# 2015_IHM.net
KiCad netlist of a schematic drawn in Altium Designer
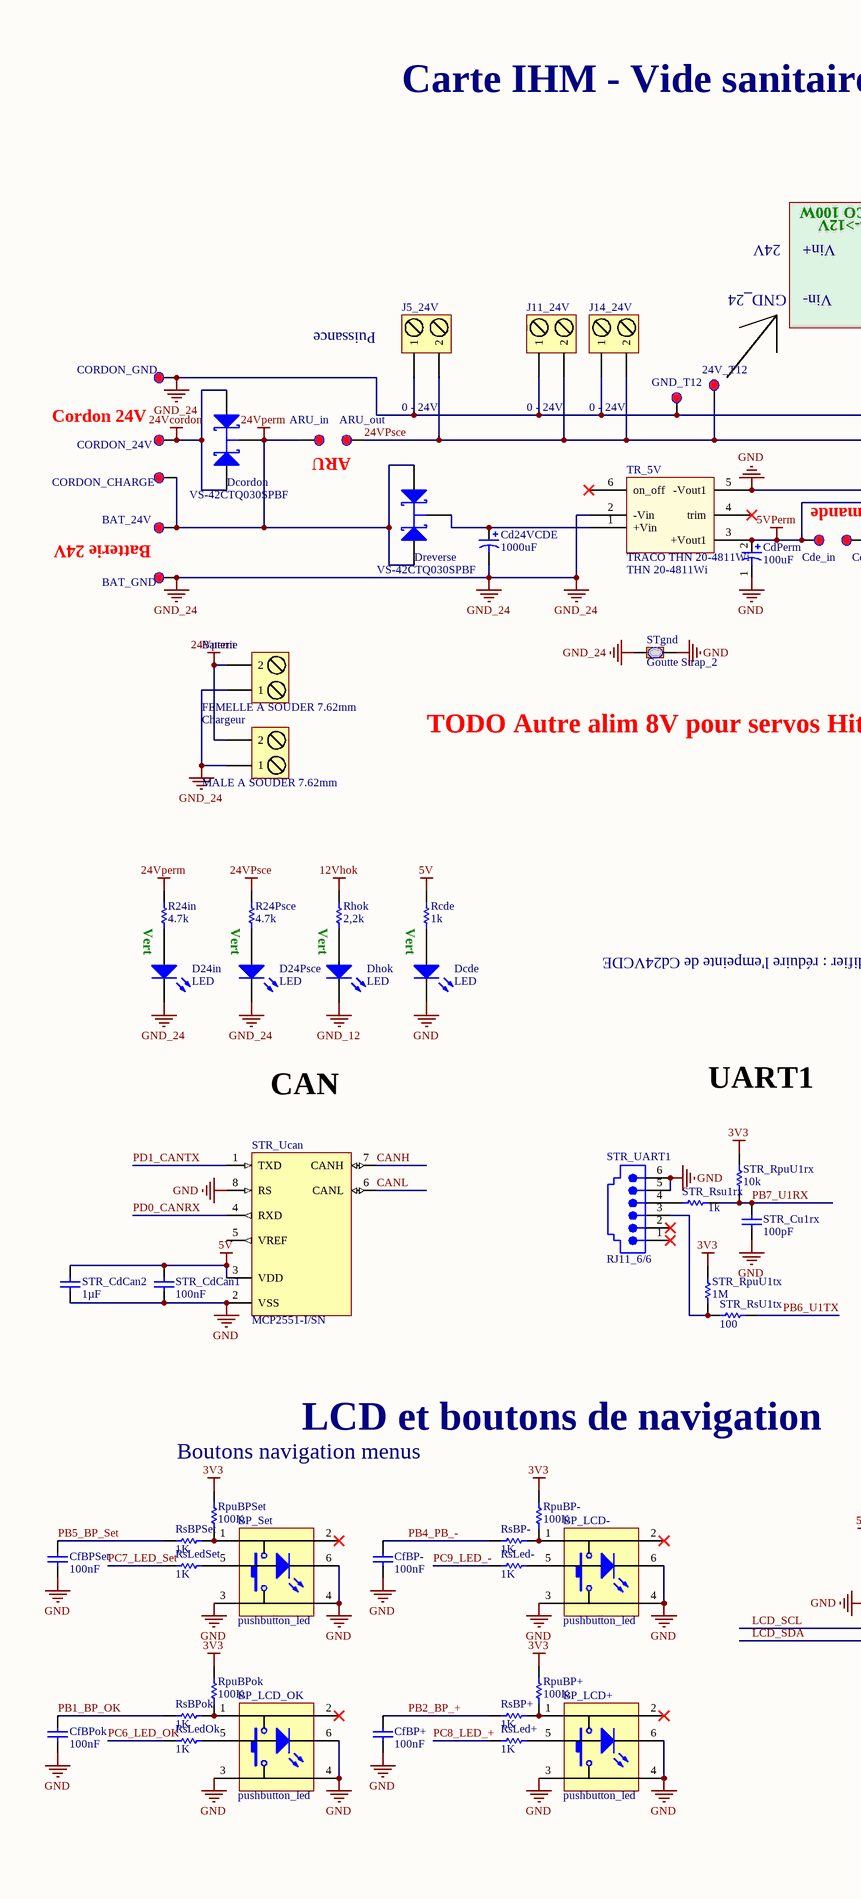
[diagram p0: 2015_IHM.SchDoc, left]
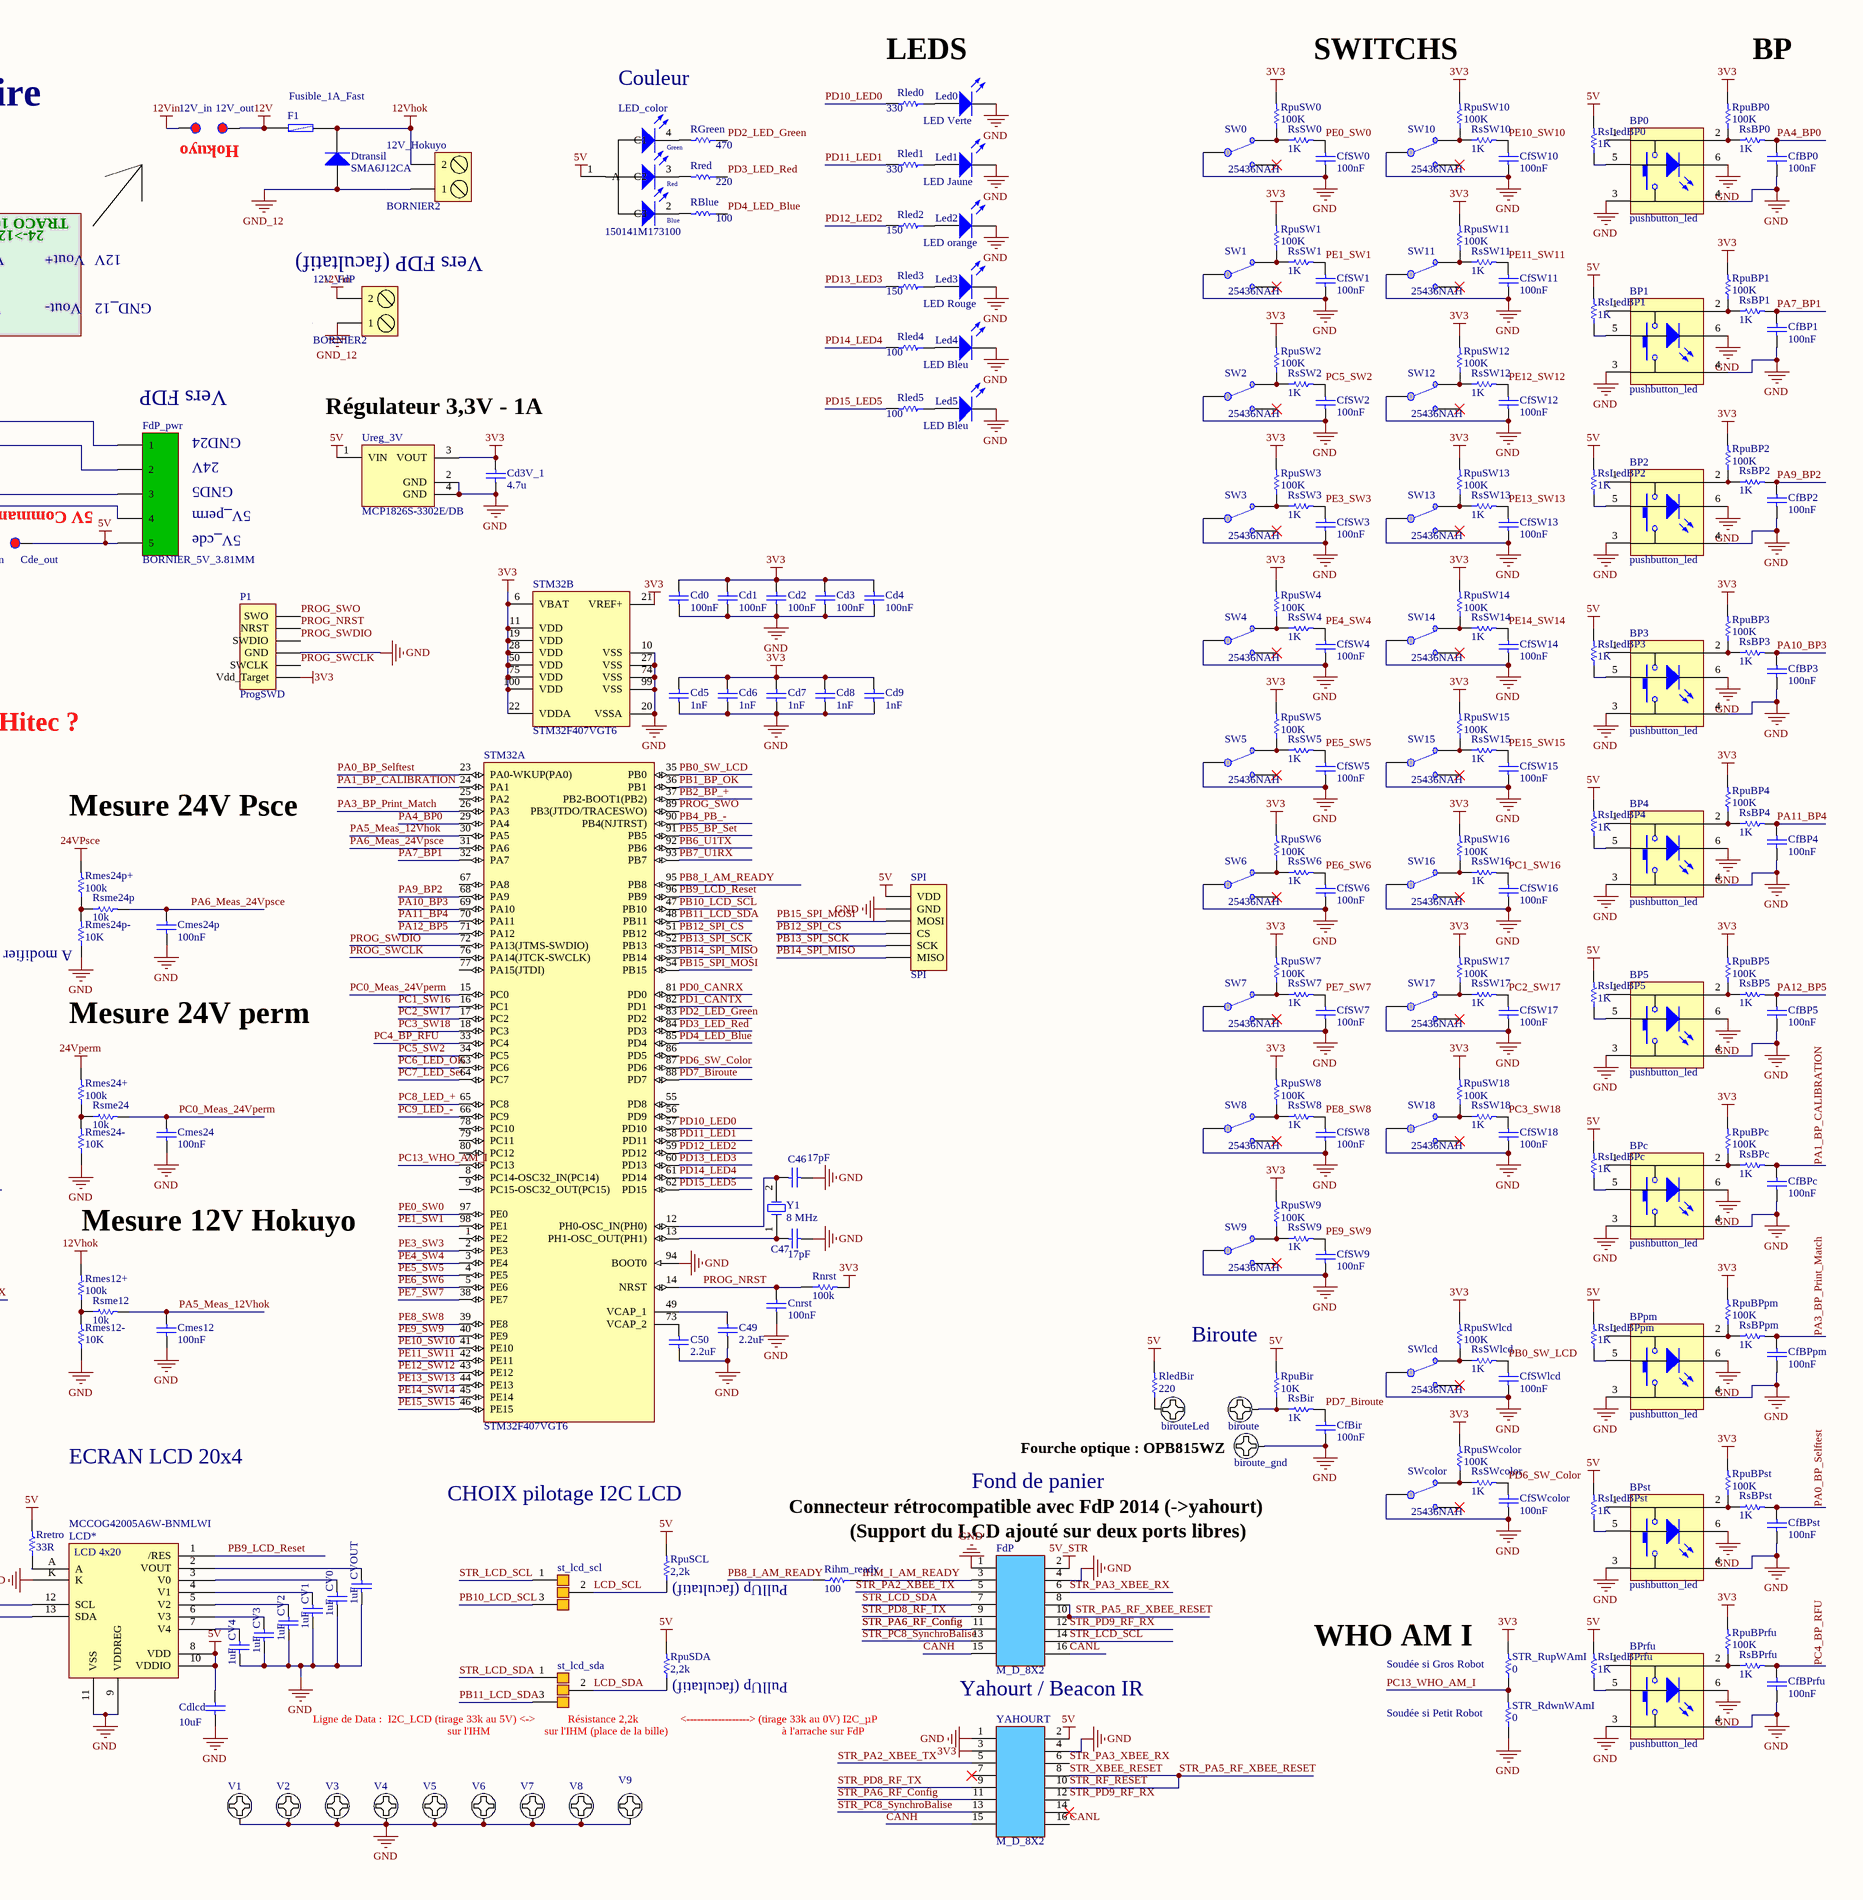
[diagram p1: 2015_IHM.SchDoc, right]

(export (version "E")
  (design (tool "Eeschema 10.0.6"))
  (components
    (comp (ref "12V_FdP")
      (value "BORNIER2")
      (footprint "BORNIER2")
      (description "Terminal blocks, 2 pins, pitch=5mm")
      (libsource (lib "Connecteur") (part "BORNIER2"))
    )
    (comp (ref "12V_Hokuyo")
      (value "BORNIER2")
      (footprint "BORNIER2_HORIZ")
      (description "Terminal blocks, 2 pins, pitch=5mm")
      (libsource (lib "Connecteur") (part "BORNIER2"))
    )
    (comp (ref "12V_in")
      (value "Name")
      (footprint "Point Test_D3_P1.6mm")
      (description "Point test")
      (fields (field (name "PUBLISHER") "Damien GUITTON"))
      (libsource (lib "DG_Connecteur") (part "Point Test"))
    )
    (comp (ref "12V_out")
      (value "Name")
      (footprint "Point Test_D3_P1.6mm")
      (description "Point test")
      (fields (field (name "PUBLISHER") "Damien GUITTON"))
      (libsource (lib "DG_Connecteur") (part "Point Test"))
    )
    (comp (ref "24V_T12")
      (value "Name")
      (footprint "Point Test_D3_P1.6mm")
      (description "Point test")
      (fields (field (name "PUBLISHER") "Damien GUITTON"))
      (libsource (lib "DG_Connecteur") (part "Point Test"))
    )
    (comp (ref "ARU_in")
      (value "Name")
      (footprint "Point Test_D3_P1.6mm")
      (description "Point test")
      (fields (field (name "PUBLISHER") "Damien GUITTON"))
      (libsource (lib "DG_Connecteur") (part "Point Test"))
    )
    (comp (ref "ARU_out")
      (value "Name")
      (footprint "Point Test_D3_P1.6mm")
      (description "Point test")
      (fields (field (name "PUBLISHER") "Damien GUITTON"))
      (libsource (lib "DG_Connecteur") (part "Point Test"))
    )
    (comp (ref "Batterie")
      (value "FEMELLE A SOUDER 7.62mm")
      (footprint "BORNIER2_FEM_COUDE")
      (description "Terminal blocks, 2 pins, pitch=5mm")
      (libsource (lib "Connecteur") (part "BORNIER2"))
    )
    (comp (ref "BAT_24V")
      (value "Name")
      (footprint "Point Test_D3_P1.6mm")
      (description "Point test")
      (fields (field (name "PUBLISHER") "Damien GUITTON"))
      (libsource (lib "DG_Connecteur") (part "Point Test"))
    )
    (comp (ref "BAT_GND")
      (value "Name")
      (footprint "Point Test_D3_P1.6mm")
      (description "Point test")
      (fields (field (name "PUBLISHER") "Damien GUITTON"))
      (libsource (lib "DG_Connecteur") (part "Point Test"))
    )
    (comp (ref "biroute")
      (value "Pad_M3")
      (footprint "PAD_CMS_5.08x2.54")
      (description "Vis M3 X 6mm _TORX_Tête 6mm")
      (fields (field (name "PUBLISHER") "Damien Guitton"))
      (libsource (lib "_ROBOT") (part "Vis M3 X 6mm _TORX_Tête 6mm"))
    )
    (comp (ref "birouteLed")
      (value "Pad_M3")
      (footprint "PAD_CMS_5.08x2.54")
      (description "Vis M3 X 6mm _TORX_Tête 6mm")
      (fields (field (name "PUBLISHER") "Damien Guitton"))
      (libsource (lib "_ROBOT") (part "Vis M3 X 6mm _TORX_Tête 6mm"))
    )
    (comp (ref "biroute_gnd")
      (value "Pad_M3")
      (footprint "PAD_CMS_5.08x2.54")
      (description "Vis M3 X 6mm _TORX_Tête 6mm")
      (fields (field (name "PUBLISHER") "Damien Guitton"))
      (libsource (lib "_ROBOT") (part "Vis M3 X 6mm _TORX_Tête 6mm"))
    )
    (comp (ref "BP0")
      (value "pushbutton_led")
      (footprint "PUSHBUTTON_LED_SET")
      (libsource (lib "_ROBOT") (part "pushbutton_led"))
    )
    (comp (ref "BP1")
      (value "pushbutton_led")
      (footprint "PUSHBUTTON_LED_SET")
      (libsource (lib "_ROBOT") (part "pushbutton_led"))
    )
    (comp (ref "BP2")
      (value "pushbutton_led")
      (footprint "PUSHBUTTON_LED_SET")
      (libsource (lib "_ROBOT") (part "pushbutton_led"))
    )
    (comp (ref "BP3")
      (value "pushbutton_led")
      (footprint "PUSHBUTTON_LED_SET")
      (libsource (lib "_ROBOT") (part "pushbutton_led"))
    )
    (comp (ref "BP4")
      (value "pushbutton_led")
      (footprint "PUSHBUTTON_LED_SET")
      (libsource (lib "_ROBOT") (part "pushbutton_led"))
    )
    (comp (ref "BP5")
      (value "pushbutton_led")
      (footprint "PUSHBUTTON_LED_SET")
      (libsource (lib "_ROBOT") (part "pushbutton_led"))
    )
    (comp (ref "BPc")
      (value "pushbutton_led")
      (footprint "PUSHBUTTON_LED_SET")
      (libsource (lib "_ROBOT") (part "pushbutton_led"))
    )
    (comp (ref "BPpm")
      (value "pushbutton_led")
      (footprint "PUSHBUTTON_LED_SET")
      (libsource (lib "_ROBOT") (part "pushbutton_led"))
    )
    (comp (ref "BPrfu")
      (value "pushbutton_led")
      (footprint "PUSHBUTTON_LED_SET")
      (libsource (lib "_ROBOT") (part "pushbutton_led"))
    )
    (comp (ref "BPst")
      (value "pushbutton_led")
      (footprint "PUSHBUTTON_LED_SET")
      (libsource (lib "_ROBOT") (part "pushbutton_led"))
    )
    (comp (ref "BP_LCD+")
      (value "pushbutton_led")
      (footprint "PUSHBUTTON_LED_FlecheDroite")
      (libsource (lib "_ROBOT") (part "pushbutton_led"))
    )
    (comp (ref "BP_LCD-")
      (value "pushbutton_led")
      (footprint "PUSHBUTTON_LED_FlecheGauche")
      (libsource (lib "_ROBOT") (part "pushbutton_led"))
    )
    (comp (ref "BP_LCD_OK")
      (value "pushbutton_led")
      (footprint "PUSHBUTTON_LED_OK")
      (libsource (lib "_ROBOT") (part "pushbutton_led"))
    )
    (comp (ref "BP_Set")
      (value "pushbutton_led")
      (footprint "PUSHBUTTON_LED_SET")
      (libsource (lib "_ROBOT") (part "pushbutton_led"))
    )
    (comp (ref "C46")
      (value "17pF")
      (footprint "C0805_N")
      (description "Capacitor")
      (fields (field (name "PUBLISHER") "Altium Limited"))
      (libsource (lib "_ROBOT") (part "Condensateur"))
    )
    (comp (ref "C47")
      (value "17pF")
      (footprint "C0805_N")
      (description "Capacitor")
      (fields (field (name "PUBLISHER") "Altium Limited"))
      (libsource (lib "_ROBOT") (part "Condensateur"))
    )
    (comp (ref "C49")
      (value "2.2uF")
      (footprint "C0805_N")
      (description "Capacitor")
      (fields (field (name "PUBLISHER") "Altium Limited"))
      (libsource (lib "_ROBOT") (part "Condensateur"))
    )
    (comp (ref "C50")
      (value "2.2uF")
      (footprint "C0805_N")
      (description "Capacitor")
      (fields (field (name "PUBLISHER") "Altium Limited"))
      (libsource (lib "_ROBOT") (part "Condensateur"))
    )
    (comp (ref "Cd0")
      (value "100nF")
      (footprint "C0805_N")
      (description "Capacitor")
      (fields (field (name "PUBLISHER") "Altium Limited"))
      (libsource (lib "_ROBOT") (part "Condensateur"))
    )
    (comp (ref "Cd1")
      (value "100nF")
      (footprint "C0805_N")
      (description "Capacitor")
      (fields (field (name "PUBLISHER") "Altium Limited"))
      (libsource (lib "_ROBOT") (part "Condensateur"))
    )
    (comp (ref "Cd2")
      (value "100nF")
      (footprint "C0805_N")
      (description "Capacitor")
      (fields (field (name "PUBLISHER") "Altium Limited"))
      (libsource (lib "_ROBOT") (part "Condensateur"))
    )
    (comp (ref "Cd3")
      (value "100nF")
      (footprint "C0805_N")
      (description "Capacitor")
      (fields (field (name "PUBLISHER") "Altium Limited"))
      (libsource (lib "_ROBOT") (part "Condensateur"))
    )
    (comp (ref "Cd3V_1")
      (value "4.7u")
      (footprint "C0805_N")
      (description "Capacitor")
      (fields (field (name "PUBLISHER") "Altium Limited"))
      (libsource (lib "DG_Condensateur") (part "Capacitor"))
    )
    (comp (ref "Cd4")
      (value "100nF")
      (footprint "C0805_N")
      (description "Capacitor")
      (fields (field (name "PUBLISHER") "Altium Limited"))
      (libsource (lib "_ROBOT") (part "Condensateur"))
    )
    (comp (ref "Cd5")
      (value "1nF")
      (footprint "C0805_N")
      (description "Capacitor")
      (fields (field (name "PUBLISHER") "Altium Limited"))
      (libsource (lib "_ROBOT") (part "Condensateur"))
    )
    (comp (ref "Cd6")
      (value "1nF")
      (footprint "C0805_N")
      (description "Capacitor")
      (fields (field (name "PUBLISHER") "Altium Limited"))
      (libsource (lib "_ROBOT") (part "Condensateur"))
    )
    (comp (ref "Cd7")
      (value "1nF")
      (footprint "C0805_N")
      (description "Capacitor")
      (fields (field (name "PUBLISHER") "Altium Limited"))
      (libsource (lib "_ROBOT") (part "Condensateur"))
    )
    (comp (ref "Cd8")
      (value "1nF")
      (footprint "C0805_N")
      (description "Capacitor")
      (fields (field (name "PUBLISHER") "Altium Limited"))
      (libsource (lib "_ROBOT") (part "Condensateur"))
    )
    (comp (ref "Cd9")
      (value "1nF")
      (footprint "C0805_N")
      (description "Capacitor")
      (fields (field (name "PUBLISHER") "Altium Limited"))
      (libsource (lib "_ROBOT") (part "Condensateur"))
    )
    (comp (ref "Cd24VCDE")
      (value "1000uF")
      (footprint "RESISTANCE_5W")
      (description "Polarized Capacitor")
      (libsource (lib "_ROBOT") (part "Condensateur Polarise Traversant"))
    )
    (comp (ref "Cde_in")
      (value "Name")
      (footprint "Point Test_D3_P1.6mm")
      (description "Point test")
      (fields (field (name "PUBLISHER") "Damien GUITTON"))
      (libsource (lib "DG_Connecteur") (part "Point Test"))
    )
    (comp (ref "Cde_out")
      (value "Name")
      (footprint "Point Test_D3_P1.6mm")
      (description "Point test")
      (fields (field (name "PUBLISHER") "Damien GUITTON"))
      (libsource (lib "DG_Connecteur") (part "Point Test"))
    )
    (comp (ref "Cdlcd")
      (value "10uF")
      (footprint "C0805_N")
      (description "Capacitor")
      (fields (field (name "PUBLISHER") "Altium Limited"))
      (libsource (lib "_ROBOT") (part "Condensateur"))
    )
    (comp (ref "CdPerm")
      (value "100uF")
      (footprint "CONDENSATEUR_POLARISE_ELECTROLYTIQUE_RADIAL_5.08/8.9")
      (description "Polarized Capacitor")
      (libsource (lib "") (part "Condensateur Polarise Traversant_1"))
    )
    (comp (ref "CfBir")
      (value "100nF")
      (footprint "C0805_N")
      (description "Capacitor")
      (fields (field (name "PUBLISHER") "Altium Limited"))
      (libsource (lib "_ROBOT") (part "Condensateur"))
    )
    (comp (ref "CfBP+")
      (value "100nF")
      (footprint "C0805_N")
      (description "Capacitor")
      (fields (field (name "PUBLISHER") "Altium Limited"))
      (libsource (lib "_ROBOT") (part "Condensateur"))
    )
    (comp (ref "CfBP-")
      (value "100nF")
      (footprint "C0805_N")
      (description "Capacitor")
      (fields (field (name "PUBLISHER") "Altium Limited"))
      (libsource (lib "_ROBOT") (part "Condensateur"))
    )
    (comp (ref "CfBP0")
      (value "100nF")
      (footprint "C0805_N")
      (description "Capacitor")
      (fields (field (name "PUBLISHER") "Altium Limited"))
      (libsource (lib "_ROBOT") (part "Condensateur"))
    )
    (comp (ref "CfBP1")
      (value "100nF")
      (footprint "C0805_N")
      (description "Capacitor")
      (fields (field (name "PUBLISHER") "Altium Limited"))
      (libsource (lib "_ROBOT") (part "Condensateur"))
    )
    (comp (ref "CfBP2")
      (value "100nF")
      (footprint "C0805_N")
      (description "Capacitor")
      (fields (field (name "PUBLISHER") "Altium Limited"))
      (libsource (lib "_ROBOT") (part "Condensateur"))
    )
    (comp (ref "CfBP3")
      (value "100nF")
      (footprint "C0805_N")
      (description "Capacitor")
      (fields (field (name "PUBLISHER") "Altium Limited"))
      (libsource (lib "_ROBOT") (part "Condensateur"))
    )
    (comp (ref "CfBP4")
      (value "100nF")
      (footprint "C0805_N")
      (description "Capacitor")
      (fields (field (name "PUBLISHER") "Altium Limited"))
      (libsource (lib "_ROBOT") (part "Condensateur"))
    )
    (comp (ref "CfBP5")
      (value "100nF")
      (footprint "C0805_N")
      (description "Capacitor")
      (fields (field (name "PUBLISHER") "Altium Limited"))
      (libsource (lib "_ROBOT") (part "Condensateur"))
    )
    (comp (ref "CfBPc")
      (value "100nF")
      (footprint "C0805_N")
      (description "Capacitor")
      (fields (field (name "PUBLISHER") "Altium Limited"))
      (libsource (lib "_ROBOT") (part "Condensateur"))
    )
    (comp (ref "CfBPok")
      (value "100nF")
      (footprint "C0805_N")
      (description "Capacitor")
      (fields (field (name "PUBLISHER") "Altium Limited"))
      (libsource (lib "_ROBOT") (part "Condensateur"))
    )
    (comp (ref "CfBPpm")
      (value "100nF")
      (footprint "C0805_N")
      (description "Capacitor")
      (fields (field (name "PUBLISHER") "Altium Limited"))
      (libsource (lib "_ROBOT") (part "Condensateur"))
    )
    (comp (ref "CfBPrfu")
      (value "100nF")
      (footprint "C0805_N")
      (description "Capacitor")
      (fields (field (name "PUBLISHER") "Altium Limited"))
      (libsource (lib "_ROBOT") (part "Condensateur"))
    )
    (comp (ref "CfBPSet")
      (value "100nF")
      (footprint "C0805_N")
      (description "Capacitor")
      (fields (field (name "PUBLISHER") "Altium Limited"))
      (libsource (lib "_ROBOT") (part "Condensateur"))
    )
    (comp (ref "CfBPst")
      (value "100nF")
      (footprint "C0805_N")
      (description "Capacitor")
      (fields (field (name "PUBLISHER") "Altium Limited"))
      (libsource (lib "_ROBOT") (part "Condensateur"))
    )
    (comp (ref "CfSW0")
      (value "100nF")
      (footprint "C0805_N")
      (description "Capacitor")
      (fields (field (name "PUBLISHER") "Altium Limited"))
      (libsource (lib "_ROBOT") (part "Condensateur"))
    )
    (comp (ref "CfSW1")
      (value "100nF")
      (footprint "C0805_N")
      (description "Capacitor")
      (fields (field (name "PUBLISHER") "Altium Limited"))
      (libsource (lib "_ROBOT") (part "Condensateur"))
    )
    (comp (ref "CfSW2")
      (value "100nF")
      (footprint "C0805_N")
      (description "Capacitor")
      (fields (field (name "PUBLISHER") "Altium Limited"))
      (libsource (lib "_ROBOT") (part "Condensateur"))
    )
    (comp (ref "CfSW3")
      (value "100nF")
      (footprint "C0805_N")
      (description "Capacitor")
      (fields (field (name "PUBLISHER") "Altium Limited"))
      (libsource (lib "_ROBOT") (part "Condensateur"))
    )
    (comp (ref "CfSW4")
      (value "100nF")
      (footprint "C0805_N")
      (description "Capacitor")
      (fields (field (name "PUBLISHER") "Altium Limited"))
      (libsource (lib "_ROBOT") (part "Condensateur"))
    )
    (comp (ref "CfSW5")
      (value "100nF")
      (footprint "C0805_N")
      (description "Capacitor")
      (fields (field (name "PUBLISHER") "Altium Limited"))
      (libsource (lib "_ROBOT") (part "Condensateur"))
    )
    (comp (ref "CfSW6")
      (value "100nF")
      (footprint "C0805_N")
      (description "Capacitor")
      (fields (field (name "PUBLISHER") "Altium Limited"))
      (libsource (lib "_ROBOT") (part "Condensateur"))
    )
    (comp (ref "CfSW7")
      (value "100nF")
      (footprint "C0805_N")
      (description "Capacitor")
      (fields (field (name "PUBLISHER") "Altium Limited"))
      (libsource (lib "_ROBOT") (part "Condensateur"))
    )
    (comp (ref "CfSW8")
      (value "100nF")
      (footprint "C0805_N")
      (description "Capacitor")
      (fields (field (name "PUBLISHER") "Altium Limited"))
      (libsource (lib "_ROBOT") (part "Condensateur"))
    )
    (comp (ref "CfSW9")
      (value "100nF")
      (footprint "C0805_N")
      (description "Capacitor")
      (fields (field (name "PUBLISHER") "Altium Limited"))
      (libsource (lib "_ROBOT") (part "Condensateur"))
    )
    (comp (ref "CfSW10")
      (value "100nF")
      (footprint "C0805_N")
      (description "Capacitor")
      (fields (field (name "PUBLISHER") "Altium Limited"))
      (libsource (lib "_ROBOT") (part "Condensateur"))
    )
    (comp (ref "CfSW11")
      (value "100nF")
      (footprint "C0805_N")
      (description "Capacitor")
      (fields (field (name "PUBLISHER") "Altium Limited"))
      (libsource (lib "_ROBOT") (part "Condensateur"))
    )
    (comp (ref "CfSW12")
      (value "100nF")
      (footprint "C0805_N")
      (description "Capacitor")
      (fields (field (name "PUBLISHER") "Altium Limited"))
      (libsource (lib "_ROBOT") (part "Condensateur"))
    )
    (comp (ref "CfSW13")
      (value "100nF")
      (footprint "C0805_N")
      (description "Capacitor")
      (fields (field (name "PUBLISHER") "Altium Limited"))
      (libsource (lib "_ROBOT") (part "Condensateur"))
    )
    (comp (ref "CfSW14")
      (value "100nF")
      (footprint "C0805_N")
      (description "Capacitor")
      (fields (field (name "PUBLISHER") "Altium Limited"))
      (libsource (lib "_ROBOT") (part "Condensateur"))
    )
    (comp (ref "CfSW15")
      (value "100nF")
      (footprint "C0805_N")
      (description "Capacitor")
      (fields (field (name "PUBLISHER") "Altium Limited"))
      (libsource (lib "_ROBOT") (part "Condensateur"))
    )
    (comp (ref "CfSW16")
      (value "100nF")
      (footprint "C0805_N")
      (description "Capacitor")
      (fields (field (name "PUBLISHER") "Altium Limited"))
      (libsource (lib "_ROBOT") (part "Condensateur"))
    )
    (comp (ref "CfSW17")
      (value "100nF")
      (footprint "C0805_N")
      (description "Capacitor")
      (fields (field (name "PUBLISHER") "Altium Limited"))
      (libsource (lib "_ROBOT") (part "Condensateur"))
    )
    (comp (ref "CfSW18")
      (value "100nF")
      (footprint "C0805_N")
      (description "Capacitor")
      (fields (field (name "PUBLISHER") "Altium Limited"))
      (libsource (lib "_ROBOT") (part "Condensateur"))
    )
    (comp (ref "CfSWcolor")
      (value "100nF")
      (footprint "C0805_N")
      (description "Capacitor")
      (fields (field (name "PUBLISHER") "Altium Limited"))
      (libsource (lib "_ROBOT") (part "Condensateur"))
    )
    (comp (ref "CfSWlcd")
      (value "100nF")
      (footprint "C0805_N")
      (description "Capacitor")
      (fields (field (name "PUBLISHER") "Altium Limited"))
      (libsource (lib "_ROBOT") (part "Condensateur"))
    )
    (comp (ref "Chargeur")
      (value "MALE A SOUDER 7.62mm")
      (footprint "BORNIER2_FEM_COUDE")
      (description "Terminal blocks, 2 pins, pitch=5mm")
      (libsource (lib "Connecteur") (part "BORNIER2"))
    )
    (comp (ref "Cmes12")
      (value "100nF")
      (footprint "C0805_N")
      (description "Capacitor")
      (fields (field (name "PUBLISHER") "Altium Limited"))
      (libsource (lib "_ROBOT") (part "Condensateur"))
    )
    (comp (ref "Cmes24")
      (value "100nF")
      (footprint "C0805_N")
      (description "Capacitor")
      (fields (field (name "PUBLISHER") "Altium Limited"))
      (libsource (lib "_ROBOT") (part "Condensateur"))
    )
    (comp (ref "Cmes24p")
      (value "100nF")
      (footprint "C0805_N")
      (description "Capacitor")
      (fields (field (name "PUBLISHER") "Altium Limited"))
      (libsource (lib "_ROBOT") (part "Condensateur"))
    )
    (comp (ref "Cnrst")
      (value "100nF")
      (footprint "C0805_N")
      (description "Capacitor")
      (fields (field (name "PUBLISHER") "Altium Limited"))
      (libsource (lib "_ROBOT") (part "Condensateur"))
    )
    (comp (ref "CORDON_24V")
      (value "Name")
      (footprint "Point Test_D3_P1.6mm")
      (description "Point test")
      (fields (field (name "PUBLISHER") "Damien GUITTON"))
      (libsource (lib "DG_Connecteur") (part "Point Test"))
    )
    (comp (ref "CORDON_CHARGE")
      (value "Name")
      (footprint "Point Test_D3_P1.6mm")
      (description "Point test")
      (fields (field (name "PUBLISHER") "Damien GUITTON"))
      (libsource (lib "DG_Connecteur") (part "Point Test"))
    )
    (comp (ref "CORDON_GND")
      (value "Name")
      (footprint "Point Test_D3_P1.6mm")
      (description "Point test")
      (fields (field (name "PUBLISHER") "Damien GUITTON"))
      (libsource (lib "DG_Connecteur") (part "Point Test"))
    )
    (comp (ref "CV0")
      (value "1uF")
      (footprint "C0805_N")
      (description "Capacitor")
      (fields (field (name "PUBLISHER") "Altium Limited"))
      (libsource (lib "_ROBOT") (part "Condensateur"))
    )
    (comp (ref "CV1")
      (value "1uF")
      (footprint "C0805_N")
      (description "Capacitor")
      (fields (field (name "PUBLISHER") "Altium Limited"))
      (libsource (lib "_ROBOT") (part "Condensateur"))
    )
    (comp (ref "CV2")
      (value "1uF")
      (footprint "C0805_N")
      (description "Capacitor")
      (fields (field (name "PUBLISHER") "Altium Limited"))
      (libsource (lib "_ROBOT") (part "Condensateur"))
    )
    (comp (ref "CV3")
      (value "1uF")
      (footprint "C0805_N")
      (description "Capacitor")
      (fields (field (name "PUBLISHER") "Altium Limited"))
      (libsource (lib "_ROBOT") (part "Condensateur"))
    )
    (comp (ref "CV4")
      (value "1uF")
      (footprint "C0805_N")
      (description "Capacitor")
      (fields (field (name "PUBLISHER") "Altium Limited"))
      (libsource (lib "_ROBOT") (part "Condensateur"))
    )
    (comp (ref "CVOUT")
      (value "1uF")
      (footprint "C0805_N")
      (description "Capacitor")
      (fields (field (name "PUBLISHER") "Altium Limited"))
      (libsource (lib "_ROBOT") (part "Condensateur"))
    )
    (comp (ref "D24in")
      (value "LED")
      (footprint "LED_0805")
      (description "Typical LED")
      (fields (field (name "PUBLISHER") "Altium Limited"))
      (libsource (lib "_ROBOT") (part "LED"))
    )
    (comp (ref "D24Psce")
      (value "LED")
      (footprint "LED_0805")
      (description "Typical LED")
      (fields (field (name "PUBLISHER") "Altium Limited"))
      (libsource (lib "_ROBOT") (part "LED"))
    )
    (comp (ref "Dcde")
      (value "LED")
      (footprint "LED_0805")
      (description "Typical LED")
      (fields (field (name "PUBLISHER") "Altium Limited"))
      (libsource (lib "_ROBOT") (part "LED"))
    )
    (comp (ref "Dcordon")
      (value "VS-42CTQ030SPBF")
      (footprint "D2Pak (123)")
      (description "DIODE SCHOTTKY DOUBLE")
      (fields (field (name "MANUFACTURER PART NUMBER") "BAT54C") (field (name "MANUFACTURER") "ZETEX"))
      (libsource (lib "_ROBOT") (part "Diode Shottky double BAT54C"))
    )
    (comp (ref "Dhok")
      (value "LED")
      (footprint "LED_0805")
      (description "Typical LED")
      (fields (field (name "PUBLISHER") "Altium Limited"))
      (libsource (lib "_ROBOT") (part "LED"))
    )
    (comp (ref "Dreverse")
      (value "VS-42CTQ030SPBF")
      (footprint "D2Pak (123)")
      (description "DIODE SCHOTTKY DOUBLE")
      (fields (field (name "MANUFACTURER PART NUMBER") "BAT54C") (field (name "MANUFACTURER") "ZETEX"))
      (libsource (lib "_ROBOT") (part "Diode Shottky double BAT54C"))
    )
    (comp (ref "Dtransil")
      (value "SMA6J12CA")
      (footprint "DO214AC")
      (description "1 Amp General Purpose Rectifier")
      (fields (field (name "PUBLISHER") "Altium Limited"))
      (libsource (lib "Miscellaneous Devices") (part "Diode 1N4001"))
    )
    (comp (ref "F1")
      (value "Fusible_1A_Fast")
      (footprint "R0805_N")
      (description "Fuse")
      (fields (field (name "PUBLISHER") "Altium Limited"))
      (libsource (lib "DG_Fusible") (part "Fusible_SMD"))
    )
    (comp (ref "FdP")
      (value "BARRETTE_8 CONTACTS_2 RANGEES_MALE_DROITE")
      (footprint "HE10/16_M_D_B P")
      (fields (field (name "TYPE") "M_D_8X2"))
      (libsource (lib "connecteurs") (part "BARRETTE_8 CONTACTS_2 RANGEES_MALE_DROITE"))
    )
    (comp (ref "FdP_pwr")
      (value "BORNIER_5V_3.81MM")
      (footprint "BORNIER_5V_3.5MM_femelle_0")
      (libsource (lib "Connecteur") (part "BORNIER_5V_3.81MM"))
    )
    (comp (ref "GND_T12")
      (value "Name")
      (footprint "Point Test_D3_P1.6mm")
      (description "Point test")
      (fields (field (name "PUBLISHER") "Damien GUITTON"))
      (libsource (lib "DG_Connecteur") (part "Point Test"))
    )
    (comp (ref "J5_24V")
      (value "0 - 24V")
      (footprint "BORNIER2_FEM_COUDE")
      (description "Terminal blocks, 2 pins, pitch=5mm")
      (libsource (lib "miniprojet") (part "BORNIER2"))
    )
    (comp (ref "J11_24V")
      (value "0 - 24V")
      (footprint "BORNIER2_FEM_COUDE")
      (description "Terminal blocks, 2 pins, pitch=5mm")
      (libsource (lib "miniprojet") (part "BORNIER2"))
    )
    (comp (ref "J14_24V")
      (value "0 - 24V")
      (footprint "BORNIER2_FEM_COUDE")
      (description "Terminal blocks, 2 pins, pitch=5mm")
      (libsource (lib "miniprojet") (part "BORNIER2"))
    )
    (comp (ref "LCD*")
      (value "MCCOG42005A6W-BNMLWI")
      (footprint "LCD_4X20_MIDAS")
      (libsource (lib "_ROBOT") (part "LCD_MIDAS_4x20"))
    )
    (comp (ref "Led0")
      (value "LED Verte")
      (footprint "LED_0805")
      (description "Typical LED")
      (fields (field (name "PUBLISHER") "Altium Limited"))
      (libsource (lib "DG_LED") (part "LED"))
    )
    (comp (ref "Led1")
      (value "LED Jaune")
      (footprint "LED_0805")
      (description "Typical LED")
      (fields (field (name "PUBLISHER") "Altium Limited"))
      (libsource (lib "DG_LED") (part "LED"))
    )
    (comp (ref "Led2")
      (value "LED orange")
      (footprint "LED_0805")
      (description "Typical LED")
      (fields (field (name "PUBLISHER") "Altium Limited"))
      (libsource (lib "DG_LED") (part "LED"))
    )
    (comp (ref "Led3")
      (value "LED Rouge")
      (footprint "LED_0805")
      (description "Typical LED")
      (fields (field (name "PUBLISHER") "Altium Limited"))
      (libsource (lib "DG_LED") (part "LED"))
    )
    (comp (ref "Led4")
      (value "LED Bleu")
      (footprint "LED_0805")
      (description "Typical LED")
      (fields (field (name "PUBLISHER") "Altium Limited"))
      (libsource (lib "DG_LED") (part "LED"))
    )
    (comp (ref "Led5")
      (value "LED Bleu")
      (footprint "LED_0805")
      (description "Typical LED")
      (fields (field (name "PUBLISHER") "Altium Limited"))
      (libsource (lib "DG_LED") (part "LED"))
    )
    (comp (ref "LED_color")
      (value "150141M173100")
      (footprint "3528")
      (description "SMD Full-Color Top LED, WL-SFTW, Red & Green & Blue")
      (fields
        (field (name "MANUFACTURER") "Würth Elektronik eiSos GmbH")
        (field (name "CREATED BY") "Christin Otto")
      )
      (libsource (lib "WL-SFTW") (part "WL-SFTW 3528 150141M173100"))
    )
    (comp (ref "P1")
      (value "ProgSWD")
      (footprint "HDR1X6")
      (description "Header, 6-Pin")
      (fields (field (name "PUBLISHER") "Altium Limited"))
      (libsource (lib "") (part "Header 6_1"))
    )
    (comp (ref "R24in")
      (value "4.7k")
      (footprint "R1206_N")
      (description "Resistor")
      (fields (field (name "PUBLISHER") "Altium Limited"))
      (libsource (lib "_ROBOT") (part "Resistor"))
    )
    (comp (ref "R24Psce")
      (value "4.7k")
      (footprint "R1206_N")
      (description "Resistor")
      (fields (field (name "PUBLISHER") "Altium Limited"))
      (libsource (lib "_ROBOT") (part "Resistor"))
    )
    (comp (ref "RBlue")
      (value "100")
      (footprint "R1206_N")
      (description "Resistor")
      (fields (field (name "PUBLISHER") "Altium Limited"))
      (libsource (lib "_ROBOT") (part "Resistor"))
    )
    (comp (ref "Rcde")
      (value "1k")
      (footprint "R1206_N")
      (description "Resistor")
      (fields (field (name "PUBLISHER") "Altium Limited"))
      (libsource (lib "_ROBOT") (part "Resistor"))
    )
    (comp (ref "RGreen")
      (value "470")
      (footprint "R1206_N")
      (description "Resistor")
      (fields (field (name "PUBLISHER") "Altium Limited"))
      (libsource (lib "_ROBOT") (part "Resistor"))
    )
    (comp (ref "Rhok")
      (value "2,2k")
      (footprint "R1206_N")
      (description "Resistor")
      (fields (field (name "PUBLISHER") "Altium Limited"))
      (libsource (lib "_ROBOT") (part "Resistor"))
    )
    (comp (ref "Rihm_ready")
      (value "100")
      (footprint "R1206_N")
      (description "Resistor")
      (fields (field (name "PUBLISHER") "Altium Limited"))
      (libsource (lib "_ROBOT") (part "Resistor"))
    )
    (comp (ref "Rled0")
      (value "330")
      (footprint "R1206_N")
      (description "Resistor")
      (fields (field (name "PUBLISHER") "Altium Limited"))
      (libsource (lib "_ROBOT") (part "Resistor"))
    )
    (comp (ref "Rled1")
      (value "330")
      (footprint "R1206_N")
      (description "Resistor")
      (fields (field (name "PUBLISHER") "Altium Limited"))
      (libsource (lib "_ROBOT") (part "Resistor"))
    )
    (comp (ref "Rled2")
      (value "150")
      (footprint "R1206_N")
      (description "Resistor")
      (fields (field (name "PUBLISHER") "Altium Limited"))
      (libsource (lib "_ROBOT") (part "Resistor"))
    )
    (comp (ref "Rled3")
      (value "150")
      (footprint "R1206_N")
      (description "Resistor")
      (fields (field (name "PUBLISHER") "Altium Limited"))
      (libsource (lib "_ROBOT") (part "Resistor"))
    )
    (comp (ref "Rled4")
      (value "100")
      (footprint "R1206_N")
      (description "Resistor")
      (fields (field (name "PUBLISHER") "Altium Limited"))
      (libsource (lib "_ROBOT") (part "Resistor"))
    )
    (comp (ref "Rled5")
      (value "100")
      (footprint "R1206_N")
      (description "Resistor")
      (fields (field (name "PUBLISHER") "Altium Limited"))
      (libsource (lib "_ROBOT") (part "Resistor"))
    )
    (comp (ref "RledBir")
      (value "220")
      (footprint "R1206_N")
      (description "Resistor")
      (fields (field (name "PUBLISHER") "Altium Limited"))
      (libsource (lib "_ROBOT") (part "Resistor"))
    )
    (comp (ref "Rmes12+")
      (value "100k")
      (footprint "R1206_N")
      (description "Resistor")
      (fields (field (name "PUBLISHER") "Altium Limited"))
      (libsource (lib "_ROBOT") (part "Resistor"))
    )
    (comp (ref "Rmes12-")
      (value "10K")
      (footprint "R1206_N")
      (description "Resistor")
      (fields (field (name "PUBLISHER") "Altium Limited"))
      (libsource (lib "_ROBOT") (part "Resistor"))
    )
    (comp (ref "Rmes24+")
      (value "100k")
      (footprint "R1206_N")
      (description "Resistor")
      (fields (field (name "PUBLISHER") "Altium Limited"))
      (libsource (lib "_ROBOT") (part "Resistor"))
    )
    (comp (ref "Rmes24-")
      (value "10K")
      (footprint "R1206_N")
      (description "Resistor")
      (fields (field (name "PUBLISHER") "Altium Limited"))
      (libsource (lib "_ROBOT") (part "Resistor"))
    )
    (comp (ref "Rmes24p+")
      (value "100k")
      (footprint "R1206_N")
      (description "Resistor")
      (fields (field (name "PUBLISHER") "Altium Limited"))
      (libsource (lib "_ROBOT") (part "Resistor"))
    )
    (comp (ref "Rmes24p-")
      (value "10K")
      (footprint "R1206_N")
      (description "Resistor")
      (fields (field (name "PUBLISHER") "Altium Limited"))
      (libsource (lib "_ROBOT") (part "Resistor"))
    )
    (comp (ref "Rnrst")
      (value "100k")
      (footprint "R1206_N")
      (description "Resistor")
      (fields (field (name "PUBLISHER") "Altium Limited"))
      (libsource (lib "_ROBOT") (part "Resistor"))
    )
    (comp (ref "RpuBir")
      (value "10K")
      (footprint "R1206_N")
      (description "Resistor")
      (fields (field (name "PUBLISHER") "Altium Limited"))
      (libsource (lib "_ROBOT") (part "Resistor"))
    )
    (comp (ref "RpuBP+")
      (value "100K")
      (footprint "R1206_N")
      (description "Resistor")
      (fields (field (name "PUBLISHER") "Altium Limited"))
      (libsource (lib "_ROBOT") (part "Resistor"))
    )
    (comp (ref "RpuBP-")
      (value "100K")
      (footprint "R1206_N")
      (description "Resistor")
      (fields (field (name "PUBLISHER") "Altium Limited"))
      (libsource (lib "_ROBOT") (part "Resistor"))
    )
    (comp (ref "RpuBP0")
      (value "100K")
      (footprint "R1206_N")
      (description "Resistor")
      (fields (field (name "PUBLISHER") "Altium Limited"))
      (libsource (lib "_ROBOT") (part "Resistor"))
    )
    (comp (ref "RpuBP1")
      (value "100K")
      (footprint "R1206_N")
      (description "Resistor")
      (fields (field (name "PUBLISHER") "Altium Limited"))
      (libsource (lib "_ROBOT") (part "Resistor"))
    )
    (comp (ref "RpuBP2")
      (value "100K")
      (footprint "R1206_N")
      (description "Resistor")
      (fields (field (name "PUBLISHER") "Altium Limited"))
      (libsource (lib "_ROBOT") (part "Resistor"))
    )
    (comp (ref "RpuBP3")
      (value "100K")
      (footprint "R1206_N")
      (description "Resistor")
      (fields (field (name "PUBLISHER") "Altium Limited"))
      (libsource (lib "_ROBOT") (part "Resistor"))
    )
    (comp (ref "RpuBP4")
      (value "100K")
      (footprint "R1206_N")
      (description "Resistor")
      (fields (field (name "PUBLISHER") "Altium Limited"))
      (libsource (lib "_ROBOT") (part "Resistor"))
    )
    (comp (ref "RpuBP5")
      (value "100K")
      (footprint "R1206_N")
      (description "Resistor")
      (fields (field (name "PUBLISHER") "Altium Limited"))
      (libsource (lib "_ROBOT") (part "Resistor"))
    )
    (comp (ref "RpuBPc")
      (value "100K")
      (footprint "R1206_N")
      (description "Resistor")
      (fields (field (name "PUBLISHER") "Altium Limited"))
      (libsource (lib "_ROBOT") (part "Resistor"))
    )
    (comp (ref "RpuBPok")
      (value "100K")
      (footprint "R1206_N")
      (description "Resistor")
      (fields (field (name "PUBLISHER") "Altium Limited"))
      (libsource (lib "_ROBOT") (part "Resistor"))
    )
    (comp (ref "RpuBPpm")
      (value "100K")
      (footprint "R1206_N")
      (description "Resistor")
      (fields (field (name "PUBLISHER") "Altium Limited"))
      (libsource (lib "_ROBOT") (part "Resistor"))
    )
    (comp (ref "RpuBPrfu")
      (value "100K")
      (footprint "R1206_N")
      (description "Resistor")
      (fields (field (name "PUBLISHER") "Altium Limited"))
      (libsource (lib "_ROBOT") (part "Resistor"))
    )
    (comp (ref "RpuBPSet")
      (value "100K")
      (footprint "R1206_N")
      (description "Resistor")
      (fields (field (name "PUBLISHER") "Altium Limited"))
      (libsource (lib "_ROBOT") (part "Resistor"))
    )
    (comp (ref "RpuBPst")
      (value "100K")
      (footprint "R1206_N")
      (description "Resistor")
      (fields (field (name "PUBLISHER") "Altium Limited"))
      (libsource (lib "_ROBOT") (part "Resistor"))
    )
    (comp (ref "RpuSCL")
      (value "2,2k")
      (footprint "R1206_N")
      (description "Resistor")
      (fields (field (name "PUBLISHER") "Altium Limited"))
      (libsource (lib "_ROBOT") (part "Resistor"))
    )
    (comp (ref "RpuSDA")
      (value "2,2k")
      (footprint "R1206_N")
      (description "Resistor")
      (fields (field (name "PUBLISHER") "Altium Limited"))
      (libsource (lib "_ROBOT") (part "Resistor"))
    )
    (comp (ref "RpuSW0")
      (value "100K")
      (footprint "R1206_N")
      (description "Resistor")
      (fields (field (name "PUBLISHER") "Altium Limited"))
      (libsource (lib "_ROBOT") (part "Resistor"))
    )
    (comp (ref "RpuSW1")
      (value "100K")
      (footprint "R1206_N")
      (description "Resistor")
      (fields (field (name "PUBLISHER") "Altium Limited"))
      (libsource (lib "_ROBOT") (part "Resistor"))
    )
    (comp (ref "RpuSW2")
      (value "100K")
      (footprint "R1206_N")
      (description "Resistor")
      (fields (field (name "PUBLISHER") "Altium Limited"))
      (libsource (lib "_ROBOT") (part "Resistor"))
    )
    (comp (ref "RpuSW3")
      (value "100K")
      (footprint "R1206_N")
      (description "Resistor")
      (fields (field (name "PUBLISHER") "Altium Limited"))
      (libsource (lib "_ROBOT") (part "Resistor"))
    )
    (comp (ref "RpuSW4")
      (value "100K")
      (footprint "R1206_N")
      (description "Resistor")
      (fields (field (name "PUBLISHER") "Altium Limited"))
      (libsource (lib "_ROBOT") (part "Resistor"))
    )
    (comp (ref "RpuSW5")
      (value "100K")
      (footprint "R1206_N")
      (description "Resistor")
      (fields (field (name "PUBLISHER") "Altium Limited"))
      (libsource (lib "_ROBOT") (part "Resistor"))
    )
    (comp (ref "RpuSW6")
      (value "100K")
      (footprint "R1206_N")
      (description "Resistor")
      (fields (field (name "PUBLISHER") "Altium Limited"))
      (libsource (lib "_ROBOT") (part "Resistor"))
    )
    (comp (ref "RpuSW7")
      (value "100K")
      (footprint "R1206_N")
      (description "Resistor")
      (fields (field (name "PUBLISHER") "Altium Limited"))
      (libsource (lib "_ROBOT") (part "Resistor"))
    )
    (comp (ref "RpuSW8")
      (value "100K")
      (footprint "R1206_N")
      (description "Resistor")
      (fields (field (name "PUBLISHER") "Altium Limited"))
      (libsource (lib "_ROBOT") (part "Resistor"))
    )
    (comp (ref "RpuSW9")
      (value "100K")
      (footprint "R1206_N")
      (description "Resistor")
      (fields (field (name "PUBLISHER") "Altium Limited"))
      (libsource (lib "_ROBOT") (part "Resistor"))
    )
    (comp (ref "RpuSW10")
      (value "100K")
      (footprint "R1206_N")
      (description "Resistor")
      (fields (field (name "PUBLISHER") "Altium Limited"))
      (libsource (lib "_ROBOT") (part "Resistor"))
    )
    (comp (ref "RpuSW11")
      (value "100K")
      (footprint "R1206_N")
      (description "Resistor")
      (fields (field (name "PUBLISHER") "Altium Limited"))
      (libsource (lib "_ROBOT") (part "Resistor"))
    )
    (comp (ref "RpuSW12")
      (value "100K")
      (footprint "R1206_N")
      (description "Resistor")
      (fields (field (name "PUBLISHER") "Altium Limited"))
      (libsource (lib "_ROBOT") (part "Resistor"))
    )
    (comp (ref "RpuSW13")
      (value "100K")
      (footprint "R1206_N")
      (description "Resistor")
      (fields (field (name "PUBLISHER") "Altium Limited"))
      (libsource (lib "_ROBOT") (part "Resistor"))
    )
    (comp (ref "RpuSW14")
      (value "100K")
      (footprint "R1206_N")
      (description "Resistor")
      (fields (field (name "PUBLISHER") "Altium Limited"))
      (libsource (lib "_ROBOT") (part "Resistor"))
    )
    (comp (ref "RpuSW15")
      (value "100K")
      (footprint "R1206_N")
      (description "Resistor")
      (fields (field (name "PUBLISHER") "Altium Limited"))
      (libsource (lib "_ROBOT") (part "Resistor"))
    )
    (comp (ref "RpuSW16")
      (value "100K")
      (footprint "R1206_N")
      (description "Resistor")
      (fields (field (name "PUBLISHER") "Altium Limited"))
      (libsource (lib "_ROBOT") (part "Resistor"))
    )
    (comp (ref "RpuSW17")
      (value "100K")
      (footprint "R1206_N")
      (description "Resistor")
      (fields (field (name "PUBLISHER") "Altium Limited"))
      (libsource (lib "_ROBOT") (part "Resistor"))
    )
    (comp (ref "RpuSW18")
      (value "100K")
      (footprint "R1206_N")
      (description "Resistor")
      (fields (field (name "PUBLISHER") "Altium Limited"))
      (libsource (lib "_ROBOT") (part "Resistor"))
    )
    (comp (ref "RpuSWcolor")
      (value "100K")
      (footprint "R1206_N")
      (description "Resistor")
      (fields (field (name "PUBLISHER") "Altium Limited"))
      (libsource (lib "_ROBOT") (part "Resistor"))
    )
    (comp (ref "RpuSWlcd")
      (value "100K")
      (footprint "R1206_N")
      (description "Resistor")
      (fields (field (name "PUBLISHER") "Altium Limited"))
      (libsource (lib "_ROBOT") (part "Resistor"))
    )
    (comp (ref "Rred")
      (value "220")
      (footprint "R1206_N")
      (description "Resistor")
      (fields (field (name "PUBLISHER") "Altium Limited"))
      (libsource (lib "_ROBOT") (part "Resistor"))
    )
    (comp (ref "Rretro")
      (value "33R")
      (footprint "R1206_N")
      (description "Resistor")
      (fields (field (name "PUBLISHER") "Altium Limited"))
      (libsource (lib "_ROBOT") (part "Resistor"))
    )
    (comp (ref "RsBir")
      (value "1K")
      (footprint "R1206_N")
      (description "Resistor")
      (fields (field (name "PUBLISHER") "Altium Limited"))
      (libsource (lib "_ROBOT") (part "Resistor"))
    )
    (comp (ref "RsBP+")
      (value "1K")
      (footprint "R1206_N")
      (description "Resistor")
      (fields (field (name "PUBLISHER") "Altium Limited"))
      (libsource (lib "_ROBOT") (part "Resistor"))
    )
    (comp (ref "RsBP-")
      (value "1K")
      (footprint "R1206_N")
      (description "Resistor")
      (fields (field (name "PUBLISHER") "Altium Limited"))
      (libsource (lib "_ROBOT") (part "Resistor"))
    )
    (comp (ref "RsBP0")
      (value "1K")
      (footprint "R1206_N")
      (description "Resistor")
      (fields (field (name "PUBLISHER") "Altium Limited"))
      (libsource (lib "_ROBOT") (part "Resistor"))
    )
    (comp (ref "RsBP1")
      (value "1K")
      (footprint "R1206_N")
      (description "Resistor")
      (fields (field (name "PUBLISHER") "Altium Limited"))
      (libsource (lib "_ROBOT") (part "Resistor"))
    )
    (comp (ref "RsBP2")
      (value "1K")
      (footprint "R1206_N")
      (description "Resistor")
      (fields (field (name "PUBLISHER") "Altium Limited"))
      (libsource (lib "_ROBOT") (part "Resistor"))
    )
    (comp (ref "RsBP3")
      (value "1K")
      (footprint "R1206_N")
      (description "Resistor")
      (fields (field (name "PUBLISHER") "Altium Limited"))
      (libsource (lib "_ROBOT") (part "Resistor"))
    )
    (comp (ref "RsBP4")
      (value "1K")
      (footprint "R1206_N")
      (description "Resistor")
      (fields (field (name "PUBLISHER") "Altium Limited"))
      (libsource (lib "_ROBOT") (part "Resistor"))
    )
    (comp (ref "RsBP5")
      (value "1K")
      (footprint "R1206_N")
      (description "Resistor")
      (fields (field (name "PUBLISHER") "Altium Limited"))
      (libsource (lib "_ROBOT") (part "Resistor"))
    )
    (comp (ref "RsBPc")
      (value "1K")
      (footprint "R1206_N")
      (description "Resistor")
      (fields (field (name "PUBLISHER") "Altium Limited"))
      (libsource (lib "_ROBOT") (part "Resistor"))
    )
    (comp (ref "RsBPok")
      (value "1K")
      (footprint "R1206_N")
      (description "Resistor")
      (fields (field (name "PUBLISHER") "Altium Limited"))
      (libsource (lib "_ROBOT") (part "Resistor"))
    )
    (comp (ref "RsBPpm")
      (value "1K")
      (footprint "R1206_N")
      (description "Resistor")
      (fields (field (name "PUBLISHER") "Altium Limited"))
      (libsource (lib "_ROBOT") (part "Resistor"))
    )
    (comp (ref "RsBPrfu")
      (value "1K")
      (footprint "R1206_N")
      (description "Resistor")
      (fields (field (name "PUBLISHER") "Altium Limited"))
      (libsource (lib "_ROBOT") (part "Resistor"))
    )
    (comp (ref "RsBPSet")
      (value "1K")
      (footprint "R1206_N")
      (description "Resistor")
      (fields (field (name "PUBLISHER") "Altium Limited"))
      (libsource (lib "_ROBOT") (part "Resistor"))
    )
    (comp (ref "RsBPst")
      (value "1K")
      (footprint "R1206_N")
      (description "Resistor")
      (fields (field (name "PUBLISHER") "Altium Limited"))
      (libsource (lib "_ROBOT") (part "Resistor"))
    )
    (comp (ref "RsLed+")
      (value "1K")
      (footprint "R1206_N")
      (description "Resistor")
      (fields (field (name "PUBLISHER") "Altium Limited"))
      (libsource (lib "_ROBOT") (part "Resistor"))
    )
    (comp (ref "RsLed-")
      (value "1K")
      (footprint "R1206_N")
      (description "Resistor")
      (fields (field (name "PUBLISHER") "Altium Limited"))
      (libsource (lib "_ROBOT") (part "Resistor"))
    )
    (comp (ref "RsLedBP0")
      (value "1K")
      (footprint "R1206_N")
      (description "Resistor")
      (fields (field (name "PUBLISHER") "Altium Limited"))
      (libsource (lib "_ROBOT") (part "Resistor"))
    )
    (comp (ref "RsLedBP1")
      (value "1K")
      (footprint "R1206_N")
      (description "Resistor")
      (fields (field (name "PUBLISHER") "Altium Limited"))
      (libsource (lib "_ROBOT") (part "Resistor"))
    )
    (comp (ref "RsLedBP2")
      (value "1K")
      (footprint "R1206_N")
      (description "Resistor")
      (fields (field (name "PUBLISHER") "Altium Limited"))
      (libsource (lib "_ROBOT") (part "Resistor"))
    )
    (comp (ref "RsLedBP3")
      (value "1K")
      (footprint "R1206_N")
      (description "Resistor")
      (fields (field (name "PUBLISHER") "Altium Limited"))
      (libsource (lib "_ROBOT") (part "Resistor"))
    )
    (comp (ref "RsLedBP4")
      (value "1K")
      (footprint "R1206_N")
      (description "Resistor")
      (fields (field (name "PUBLISHER") "Altium Limited"))
      (libsource (lib "_ROBOT") (part "Resistor"))
    )
    (comp (ref "RsLedBP5")
      (value "1K")
      (footprint "R1206_N")
      (description "Resistor")
      (fields (field (name "PUBLISHER") "Altium Limited"))
      (libsource (lib "_ROBOT") (part "Resistor"))
    )
    (comp (ref "RsLedBPc")
      (value "1K")
      (footprint "R1206_N")
      (description "Resistor")
      (fields (field (name "PUBLISHER") "Altium Limited"))
      (libsource (lib "_ROBOT") (part "Resistor"))
    )
    (comp (ref "RsLedBPpm")
      (value "1K")
      (footprint "R1206_N")
      (description "Resistor")
      (fields (field (name "PUBLISHER") "Altium Limited"))
      (libsource (lib "_ROBOT") (part "Resistor"))
    )
    (comp (ref "RsLedBPrfu")
      (value "1K")
      (footprint "R1206_N")
      (description "Resistor")
      (fields (field (name "PUBLISHER") "Altium Limited"))
      (libsource (lib "_ROBOT") (part "Resistor"))
    )
    (comp (ref "RsLedBPst")
      (value "1K")
      (footprint "R1206_N")
      (description "Resistor")
      (fields (field (name "PUBLISHER") "Altium Limited"))
      (libsource (lib "_ROBOT") (part "Resistor"))
    )
    (comp (ref "RsLedOk")
      (value "1K")
      (footprint "R1206_N")
      (description "Resistor")
      (fields (field (name "PUBLISHER") "Altium Limited"))
      (libsource (lib "_ROBOT") (part "Resistor"))
    )
    (comp (ref "RsLedSet")
      (value "1K")
      (footprint "R1206_N")
      (description "Resistor")
      (fields (field (name "PUBLISHER") "Altium Limited"))
      (libsource (lib "_ROBOT") (part "Resistor"))
    )
    (comp (ref "Rsme12")
      (value "10k")
      (footprint "R1206_N")
      (description "Resistor")
      (fields (field (name "PUBLISHER") "Altium Limited"))
      (libsource (lib "_ROBOT") (part "Resistor"))
    )
    (comp (ref "Rsme24")
      (value "10k")
      (footprint "R1206_N")
      (description "Resistor")
      (fields (field (name "PUBLISHER") "Altium Limited"))
      (libsource (lib "_ROBOT") (part "Resistor"))
    )
    (comp (ref "Rsme24p")
      (value "10k")
      (footprint "R1206_N")
      (description "Resistor")
      (fields (field (name "PUBLISHER") "Altium Limited"))
      (libsource (lib "_ROBOT") (part "Resistor"))
    )
    (comp (ref "RsSW0")
      (value "1K")
      (footprint "R1206_N")
      (description "Resistor")
      (fields (field (name "PUBLISHER") "Altium Limited"))
      (libsource (lib "_ROBOT") (part "Resistor"))
    )
    (comp (ref "RsSW1")
      (value "1K")
      (footprint "R1206_N")
      (description "Resistor")
      (fields (field (name "PUBLISHER") "Altium Limited"))
      (libsource (lib "_ROBOT") (part "Resistor"))
    )
    (comp (ref "RsSW2")
      (value "1K")
      (footprint "R1206_N")
      (description "Resistor")
      (fields (field (name "PUBLISHER") "Altium Limited"))
      (libsource (lib "_ROBOT") (part "Resistor"))
    )
    (comp (ref "RsSW3")
      (value "1K")
      (footprint "R1206_N")
      (description "Resistor")
      (fields (field (name "PUBLISHER") "Altium Limited"))
      (libsource (lib "_ROBOT") (part "Resistor"))
    )
    (comp (ref "RsSW4")
      (value "1K")
      (footprint "R1206_N")
      (description "Resistor")
      (fields (field (name "PUBLISHER") "Altium Limited"))
      (libsource (lib "_ROBOT") (part "Resistor"))
    )
    (comp (ref "RsSW5")
      (value "1K")
      (footprint "R1206_N")
      (description "Resistor")
      (fields (field (name "PUBLISHER") "Altium Limited"))
      (libsource (lib "_ROBOT") (part "Resistor"))
    )
    (comp (ref "RsSW6")
      (value "1K")
      (footprint "R1206_N")
      (description "Resistor")
      (fields (field (name "PUBLISHER") "Altium Limited"))
      (libsource (lib "_ROBOT") (part "Resistor"))
    )
    (comp (ref "RsSW7")
      (value "1K")
      (footprint "R1206_N")
      (description "Resistor")
      (fields (field (name "PUBLISHER") "Altium Limited"))
      (libsource (lib "_ROBOT") (part "Resistor"))
    )
    (comp (ref "RsSW8")
      (value "1K")
      (footprint "R1206_N")
      (description "Resistor")
      (fields (field (name "PUBLISHER") "Altium Limited"))
      (libsource (lib "_ROBOT") (part "Resistor"))
    )
    (comp (ref "RsSW9")
      (value "1K")
      (footprint "R1206_N")
      (description "Resistor")
      (fields (field (name "PUBLISHER") "Altium Limited"))
      (libsource (lib "_ROBOT") (part "Resistor"))
    )
    (comp (ref "RsSW10")
      (value "1K")
      (footprint "R1206_N")
      (description "Resistor")
      (fields (field (name "PUBLISHER") "Altium Limited"))
      (libsource (lib "_ROBOT") (part "Resistor"))
    )
    (comp (ref "RsSW11")
      (value "1K")
      (footprint "R1206_N")
      (description "Resistor")
      (fields (field (name "PUBLISHER") "Altium Limited"))
      (libsource (lib "_ROBOT") (part "Resistor"))
    )
    (comp (ref "RsSW12")
      (value "1K")
      (footprint "R1206_N")
      (description "Resistor")
      (fields (field (name "PUBLISHER") "Altium Limited"))
      (libsource (lib "_ROBOT") (part "Resistor"))
    )
    (comp (ref "RsSW13")
      (value "1K")
      (footprint "R1206_N")
      (description "Resistor")
      (fields (field (name "PUBLISHER") "Altium Limited"))
      (libsource (lib "_ROBOT") (part "Resistor"))
    )
    (comp (ref "RsSW14")
      (value "1K")
      (footprint "R1206_N")
      (description "Resistor")
      (fields (field (name "PUBLISHER") "Altium Limited"))
      (libsource (lib "_ROBOT") (part "Resistor"))
    )
    (comp (ref "RsSW15")
      (value "1K")
      (footprint "R1206_N")
      (description "Resistor")
      (fields (field (name "PUBLISHER") "Altium Limited"))
      (libsource (lib "_ROBOT") (part "Resistor"))
    )
    (comp (ref "RsSW16")
      (value "1K")
      (footprint "R1206_N")
      (description "Resistor")
      (fields (field (name "PUBLISHER") "Altium Limited"))
      (libsource (lib "_ROBOT") (part "Resistor"))
    )
    (comp (ref "RsSW17")
      (value "1K")
      (footprint "R1206_N")
      (description "Resistor")
      (fields (field (name "PUBLISHER") "Altium Limited"))
      (libsource (lib "_ROBOT") (part "Resistor"))
    )
    (comp (ref "RsSW18")
      (value "1K")
      (footprint "R1206_N")
      (description "Resistor")
      (fields (field (name "PUBLISHER") "Altium Limited"))
      (libsource (lib "_ROBOT") (part "Resistor"))
    )
    (comp (ref "RsSWcolor")
      (value "1K")
      (footprint "R1206_N")
      (description "Resistor")
      (fields (field (name "PUBLISHER") "Altium Limited"))
      (libsource (lib "_ROBOT") (part "Resistor"))
    )
    (comp (ref "RsSWlcd")
      (value "1K")
      (footprint "R1206_N")
      (description "Resistor")
      (fields (field (name "PUBLISHER") "Altium Limited"))
      (libsource (lib "_ROBOT") (part "Resistor"))
    )
    (comp (ref "SPI")
      (value "SPI")
      (footprint "HDR1X6")
      (description "Header, 6-Pin")
      (fields (field (name "PUBLISHER") "Altium Limited"))
      (libsource (lib "DG_Connecteur") (part "Header 6"))
    )
    (comp (ref "STgnd")
      (value "Goutte Strap_2")
      (footprint "Goutte Strap_2 Pads_Clearance 0.254mm")
      (fields (field (name "PUBLISHER") "Damien Guitton"))
      (libsource (lib "DG_Connecteur") (part "Goutte Strap_2"))
    )
    (comp (ref "STM32")
      (value "STM32F407VGT6")
      (footprint "STM-LQFP100_N")
      (fields (field (name "MANUFACTURER") "STMicroelectronics"))
      (libsource (lib "STMicroelectronics STM32 F4") (part "STM32F407VGT6"))
    )
    (comp (ref "STR_CdCan1")
      (value "100nF")
      (footprint "C0805_N")
      (description "Capacitor")
      (fields (field (name "PUBLISHER") "Altium Limited"))
      (libsource (lib "_ROBOT") (part "Condensateur"))
    )
    (comp (ref "STR_CdCan2")
      (value "1µF")
      (footprint "C0805_N")
      (description "Capacitor")
      (fields (field (name "PUBLISHER") "Altium Limited"))
      (libsource (lib "_ROBOT") (part "Condensateur"))
    )
    (comp (ref "STR_Cu1rx")
      (value "100pF")
      (footprint "C0805_N")
      (description "Capacitor")
      (fields (field (name "PUBLISHER") "Altium Limited"))
      (libsource (lib "_ROBOT") (part "Condensateur"))
    )
    (comp (ref "STR_RdwnWAmI")
      (value "0")
      (footprint "R1206_N")
      (description "Resistor")
      (fields (field (name "PUBLISHER") "Altium Limited"))
      (libsource (lib "_ROBOT") (part "Resistor"))
    )
    (comp (ref "STR_RpuU1rx")
      (value "10k")
      (footprint "R1206_N")
      (description "Resistor")
      (fields (field (name "PUBLISHER") "Altium Limited"))
      (libsource (lib "_ROBOT") (part "Resistor"))
    )
    (comp (ref "STR_RpuU1tx")
      (value "1M")
      (footprint "R1206_N")
      (description "Resistor")
      (fields (field (name "PUBLISHER") "Altium Limited"))
      (libsource (lib "_ROBOT") (part "Resistor"))
    )
    (comp (ref "STR_Rsu1rx")
      (value "1k")
      (footprint "R1206_N")
      (description "Resistor")
      (fields (field (name "PUBLISHER") "Altium Limited"))
      (libsource (lib "_ROBOT") (part "Resistor"))
    )
    (comp (ref "STR_RsU1tx")
      (value "100")
      (footprint "R1206_N")
      (description "Resistor")
      (fields (field (name "PUBLISHER") "Altium Limited"))
      (libsource (lib "_ROBOT") (part "Resistor"))
    )
    (comp (ref "STR_RupWAmI")
      (value "0")
      (footprint "R1206_N")
      (description "Resistor")
      (fields (field (name "PUBLISHER") "Altium Limited"))
      (libsource (lib "_ROBOT") (part "Resistor"))
    )
    (comp (ref "STR_UART1")
      (value "RJ11_6/6")
      (footprint "RJ11_6/6 - Wurth Half Shielded Tab Down WR-MJ")
      (description "Right Angle, Standard Profile, Offset Latch DECconnect, Flangeless PCB Jack")
      (fields (field (name "PUBLISHER") "Altium Limited"))
      (libsource (lib "Connecteur") (part "RJ11_6/6"))
    )
    (comp (ref "STR_Ucan")
      (value "MCP2551-I/SN")
      (footprint "SO8_N")
      (description "High-Speed CAN Transceiver, 8-Pin SOIC, Industrial Temperature")
      (fields (field (name "PUBLISHER") "Damien Guitton"))
      (libsource (lib "Circuit intégré") (part "MCP2551-I/SN"))
    )
    (comp (ref "st_lcd_scl")
      (value "Goutte Strap_3")
      (footprint "Goutte Strap_3 PADS")
      (fields (field (name "PUBLISHER") "Damien Guitton"))
      (libsource (lib "DG_Connecteur") (part "Goutte Strap_3"))
    )
    (comp (ref "st_lcd_sda")
      (value "Goutte Strap_3")
      (footprint "Goutte Strap_3 PADS")
      (fields (field (name "PUBLISHER") "Damien Guitton"))
      (libsource (lib "DG_Connecteur") (part "Goutte Strap_3"))
    )
    (comp (ref "SW0")
      (value "25436NAH")
      (footprint "SW_UNIPOL_DROIT - Ebay - SPDT - 11x6x5")
      (description "Switch unipolaire a levier")
      (libsource (lib "_ROBOT") (part "SW SPDT- APEM Série 523x"))
    )
    (comp (ref "SW1")
      (value "25436NAH")
      (footprint "SW_UNIPOL_DROIT - Ebay - SPDT - 11x6x5")
      (description "Switch unipolaire a levier")
      (libsource (lib "_ROBOT") (part "SW SPDT- APEM Série 523x"))
    )
    (comp (ref "SW2")
      (value "25436NAH")
      (footprint "SW_UNIPOL_DROIT - Ebay - SPDT - 11x6x5")
      (description "Switch unipolaire a levier")
      (libsource (lib "_ROBOT") (part "SW SPDT- APEM Série 523x"))
    )
    (comp (ref "SW3")
      (value "25436NAH")
      (footprint "SW_UNIPOL_DROIT - Ebay - SPDT - 11x6x5")
      (description "Switch unipolaire a levier")
      (libsource (lib "_ROBOT") (part "SW SPDT- APEM Série 523x"))
    )
    (comp (ref "SW4")
      (value "25436NAH")
      (footprint "SW_UNIPOL_DROIT - Ebay - SPDT - 11x6x5")
      (description "Switch unipolaire a levier")
      (libsource (lib "_ROBOT") (part "SW SPDT- APEM Série 523x"))
    )
    (comp (ref "SW5")
      (value "25436NAH")
      (footprint "SW_UNIPOL_DROIT - Ebay - SPDT - 11x6x5")
      (description "Switch unipolaire a levier")
      (libsource (lib "_ROBOT") (part "SW SPDT- APEM Série 523x"))
    )
    (comp (ref "SW6")
      (value "25436NAH")
      (footprint "SW_UNIPOL_DROIT - Ebay - SPDT - 11x6x5")
      (description "Switch unipolaire a levier")
      (libsource (lib "_ROBOT") (part "SW SPDT- APEM Série 523x"))
    )
    (comp (ref "SW7")
      (value "25436NAH")
      (footprint "SW_UNIPOL_DROIT - Ebay - SPDT - 11x6x5")
      (description "Switch unipolaire a levier")
      (libsource (lib "_ROBOT") (part "SW SPDT- APEM Série 523x"))
    )
    (comp (ref "SW8")
      (value "25436NAH")
      (footprint "SW_UNIPOL_DROIT - Ebay - SPDT - 11x6x5")
      (description "Switch unipolaire a levier")
      (libsource (lib "_ROBOT") (part "SW SPDT- APEM Série 523x"))
    )
    (comp (ref "SW9")
      (value "25436NAH")
      (footprint "SW_UNIPOL_DROIT - Ebay - SPDT - 11x6x5")
      (description "Switch unipolaire a levier")
      (libsource (lib "_ROBOT") (part "SW SPDT- APEM Série 523x"))
    )
    (comp (ref "SW10")
      (value "25436NAH")
      (footprint "SW_UNIPOL_DROIT - Ebay - SPDT - 11x6x5")
      (description "Switch unipolaire a levier")
      (libsource (lib "_ROBOT") (part "SW SPDT- APEM Série 523x"))
    )
    (comp (ref "SW11")
      (value "25436NAH")
      (footprint "SW_UNIPOL_DROIT - Ebay - SPDT - 11x6x5")
      (description "Switch unipolaire a levier")
      (libsource (lib "_ROBOT") (part "SW SPDT- APEM Série 523x"))
    )
    (comp (ref "SW12")
      (value "25436NAH")
      (footprint "SW_UNIPOL_DROIT - Ebay - SPDT - 11x6x5")
      (description "Switch unipolaire a levier")
      (libsource (lib "_ROBOT") (part "SW SPDT- APEM Série 523x"))
    )
    (comp (ref "SW13")
      (value "25436NAH")
      (footprint "SW_UNIPOL_DROIT - Ebay - SPDT - 11x6x5")
      (description "Switch unipolaire a levier")
      (libsource (lib "_ROBOT") (part "SW SPDT- APEM Série 523x"))
    )
    (comp (ref "SW14")
      (value "25436NAH")
      (footprint "SW_UNIPOL_DROIT - Ebay - SPDT - 11x6x5")
      (description "Switch unipolaire a levier")
      (libsource (lib "_ROBOT") (part "SW SPDT- APEM Série 523x"))
    )
    (comp (ref "SW15")
      (value "25436NAH")
      (footprint "SW_UNIPOL_DROIT - Ebay - SPDT - 11x6x5")
      (description "Switch unipolaire a levier")
      (libsource (lib "_ROBOT") (part "SW SPDT- APEM Série 523x"))
    )
    (comp (ref "SW16")
      (value "25436NAH")
      (footprint "SW_UNIPOL_DROIT - Ebay - SPDT - 11x6x5")
      (description "Switch unipolaire a levier")
      (libsource (lib "_ROBOT") (part "SW SPDT- APEM Série 523x"))
    )
    (comp (ref "SW17")
      (value "25436NAH")
      (footprint "SW_UNIPOL_DROIT - Ebay - SPDT - 11x6x5")
      (description "Switch unipolaire a levier")
      (libsource (lib "_ROBOT") (part "SW SPDT- APEM Série 523x"))
    )
    (comp (ref "SW18")
      (value "25436NAH")
      (footprint "SW_UNIPOL_DROIT - Ebay - SPDT - 11x6x5")
      (description "Switch unipolaire a levier")
      (libsource (lib "_ROBOT") (part "SW SPDT- APEM Série 523x"))
    )
    (comp (ref "SWcolor")
      (value "25436NAH")
      (footprint "SW_UNIPOL_DROIT - APEM 18235")
      (description "Switch unipolaire a levier")
      (libsource (lib "_ROBOT") (part "SW SPDT- APEM Série 523x"))
    )
    (comp (ref "SWlcd")
      (value "25436NAH")
      (footprint "SW_UNIPOL_DROIT - Ebay - SPDT - 11x6x5")
      (description "Switch unipolaire a levier")
      (libsource (lib "_ROBOT") (part "SW SPDT- APEM Série 523x"))
    )
    (comp (ref "TR_5V")
      (value "TRACO THN 20-4811Wi")
      (footprint "TRACO_THN20")
      (description "Traco 20W 24V to 5V*4A")
      (fields (field (name "REF") "THN 20-4811Wi"))
      (libsource (lib "_ROBOT") (part "TRACO THN 20-4811Wi"))
    )
    (comp (ref "Ureg_3V")
      (value "MCP1826S-3302E/DB")
      (footprint "SOT223-4N")
      (description "1000 mA, Low Voltage, Low Quiescent Current LDO Regulator, 3-Pin SOT-223, Extended Temperature")
      (fields (field (name "PUBLISHER") "Altium Limited"))
      (libsource (lib "Microchip Power Mgt Line Regulator") (part "MCP1826S-3302E/DB"))
    )
    (comp (ref "V1")
      (value "Pad_M3")
      (footprint "M3x6mm")
      (description "Vis M3 X 6mm _TORX_Tête 6mm")
      (fields (field (name "PUBLISHER") "Damien Guitton"))
      (libsource (lib "_ROBOT") (part "Vis M3 X 6mm _TORX_Tête 6mm"))
    )
    (comp (ref "V2")
      (value "Pad_M3")
      (footprint "M3x6mm")
      (description "Vis M3 X 6mm _TORX_Tête 6mm")
      (fields (field (name "PUBLISHER") "Damien Guitton"))
      (libsource (lib "_ROBOT") (part "Vis M3 X 6mm _TORX_Tête 6mm"))
    )
    (comp (ref "V3")
      (value "Pad_M3")
      (footprint "M3x6mm")
      (description "Vis M3 X 6mm _TORX_Tête 6mm")
      (fields (field (name "PUBLISHER") "Damien Guitton"))
      (libsource (lib "_ROBOT") (part "Vis M3 X 6mm _TORX_Tête 6mm"))
    )
    (comp (ref "V4")
      (value "Pad_M3")
      (footprint "M3x6mm")
      (description "Vis M3 X 6mm _TORX_Tête 6mm")
      (fields (field (name "PUBLISHER") "Damien Guitton"))
      (libsource (lib "_ROBOT") (part "Vis M3 X 6mm _TORX_Tête 6mm"))
    )
    (comp (ref "V5")
      (value "Pad_M3")
      (footprint "M3x6mm")
      (description "Vis M3 X 6mm _TORX_Tête 6mm")
      (fields (field (name "PUBLISHER") "Damien Guitton"))
      (libsource (lib "_ROBOT") (part "Vis M3 X 6mm _TORX_Tête 6mm"))
    )
    (comp (ref "V6")
      (value "Pad_M3")
      (footprint "M3x6mm")
      (description "Vis M3 X 6mm _TORX_Tête 6mm")
      (fields (field (name "PUBLISHER") "Damien Guitton"))
      (libsource (lib "_ROBOT") (part "Vis M3 X 6mm _TORX_Tête 6mm"))
    )
    (comp (ref "V7")
      (value "Pad_M3")
      (footprint "M3x6mm")
      (description "Vis M3 X 6mm _TORX_Tête 6mm")
      (fields (field (name "PUBLISHER") "Damien Guitton"))
      (libsource (lib "_ROBOT") (part "Vis M3 X 6mm _TORX_Tête 6mm"))
    )
    (comp (ref "V8")
      (value "Pad_M3")
      (footprint "M3x6mm")
      (description "Vis M3 X 6mm _TORX_Tête 6mm")
      (fields (field (name "PUBLISHER") "Damien Guitton"))
      (libsource (lib "_ROBOT") (part "Vis M3 X 6mm _TORX_Tête 6mm"))
    )
    (comp (ref "V9")
      (value "Pad_M3")
      (footprint "M3x6mm")
      (description "Vis M3 X 6mm _TORX_Tête 6mm")
      (fields (field (name "PUBLISHER") "Damien Guitton"))
      (libsource (lib "_ROBOT") (part "Vis M3 X 6mm _TORX_Tête 6mm"))
    )
    (comp (ref "Y1")
      (value "8 MHz")
      (footprint "HC49/4H_SMX")
      (description "Crystal Oscillator")
      (fields (field (name "PUBLISHER") "Altium Limited"))
      (libsource (lib "_ROBOT") (part "Quartz"))
    )
    (comp (ref "YAHOURT")
      (value "BARRETTE_8 CONTACTS_2 RANGEES_MALE_DROITE")
      (footprint "HE10/16_M_D_B P")
      (fields (field (name "TYPE") "M_D_8X2"))
      (libsource (lib "connecteurs") (part "BARRETTE_8 CONTACTS_2 RANGEES_MALE_DROITE"))
    )
  )
  (nets
    (net (code "1") (name "/CANH") (class "Default")
      (node (ref "FdP") (pin "15") (pinfunction "15_15") (pintype "passive"))
      (node (ref "STR_Ucan") (pin "7") (pinfunction "CANH_7") (pintype "bidirectional"))
      (node (ref "YAHOURT") (pin "15") (pinfunction "15_15") (pintype "passive"))
    )
    (net (code "2") (name "/CANL") (class "Default")
      (node (ref "FdP") (pin "16") (pinfunction "16_16") (pintype "passive"))
      (node (ref "STR_Ucan") (pin "6") (pinfunction "CANL_6") (pintype "bidirectional"))
      (node (ref "YAHOURT") (pin "16") (pinfunction "16_16") (pintype "passive"))
    )
    (net (code "3") (name "/IHM_I_AM_READY") (class "Default")
      (node (ref "FdP") (pin "3") (pinfunction "3_3") (pintype "passive"))
      (node (ref "Rihm_ready") (pin "1") (pinfunction "1_1") (pintype "passive"))
    )
    (net (code "4") (name "/LCD_SCL") (class "Default")
      (node (ref "LCD*") (pin "12") (pinfunction "SCL_12") (pintype "passive"))
      (node (ref "RpuSCL") (pin "1") (pinfunction "1_1") (pintype "passive"))
      (node (ref "st_lcd_scl") (pin "2") (pinfunction "2_2") (pintype "passive"))
    )
    (net (code "5") (name "/LCD_SDA") (class "Default")
      (node (ref "LCD*") (pin "13") (pinfunction "SDA_13") (pintype "passive"))
      (node (ref "RpuSDA") (pin "1") (pinfunction "1_1") (pintype "passive"))
      (node (ref "st_lcd_sda") (pin "2") (pinfunction "2_2") (pintype "passive"))
    )
    (net (code "6") (name "/PA0_BP_Selftest") (class "Default")
      (node (ref "CfBPst") (pin "2") (pinfunction "2_2") (pintype "passive"))
      (node (ref "RsBPst") (pin "2") (pinfunction "2_2") (pintype "passive"))
      (node (ref "STM32") (pin "23") (pinfunction "PA0-WKUP(PA0)_23") (pintype "bidirectional"))
    )
    (net (code "7") (name "/PA1_BP_CALIBRATION") (class "Default")
      (node (ref "CfBPc") (pin "2") (pinfunction "2_2") (pintype "passive"))
      (node (ref "RsBPc") (pin "2") (pinfunction "2_2") (pintype "passive"))
      (node (ref "STM32") (pin "24") (pinfunction "PA1_24") (pintype "bidirectional"))
    )
    (net (code "8") (name "/PA3_BP_Print_Match") (class "Default")
      (node (ref "CfBPpm") (pin "2") (pinfunction "2_2") (pintype "passive"))
      (node (ref "RsBPpm") (pin "2") (pinfunction "2_2") (pintype "passive"))
      (node (ref "STM32") (pin "26") (pinfunction "PA3_26") (pintype "bidirectional"))
    )
    (net (code "9") (name "/PA4_BP0") (class "Default")
      (node (ref "CfBP0") (pin "2") (pinfunction "2_2") (pintype "passive"))
      (node (ref "RsBP0") (pin "2") (pinfunction "2_2") (pintype "passive"))
      (node (ref "STM32") (pin "29") (pinfunction "PA4_29") (pintype "bidirectional"))
    )
    (net (code "10") (name "/PA5_Meas_12Vhok") (class "Default")
      (node (ref "Cmes12") (pin "2") (pinfunction "2_2") (pintype "passive"))
      (node (ref "Rsme12") (pin "2") (pinfunction "2_2") (pintype "passive"))
      (node (ref "STM32") (pin "30") (pinfunction "PA5_30") (pintype "bidirectional"))
    )
    (net (code "11") (name "/PA6_Meas_24Vpsce") (class "Default")
      (node (ref "Cmes24p") (pin "2") (pinfunction "2_2") (pintype "passive"))
      (node (ref "Rsme24p") (pin "2") (pinfunction "2_2") (pintype "passive"))
      (node (ref "STM32") (pin "31") (pinfunction "PA6_31") (pintype "bidirectional"))
    )
    (net (code "12") (name "/PA7_BP1") (class "Default")
      (node (ref "CfBP1") (pin "2") (pinfunction "2_2") (pintype "passive"))
      (node (ref "RsBP1") (pin "2") (pinfunction "2_2") (pintype "passive"))
      (node (ref "STM32") (pin "32") (pinfunction "PA7_32") (pintype "bidirectional"))
    )
    (net (code "13") (name "/PA9_BP2") (class "Default")
      (node (ref "CfBP2") (pin "2") (pinfunction "2_2") (pintype "passive"))
      (node (ref "RsBP2") (pin "2") (pinfunction "2_2") (pintype "passive"))
      (node (ref "STM32") (pin "68") (pinfunction "PA9_68") (pintype "bidirectional"))
    )
    (net (code "14") (name "/PA10_BP3") (class "Default")
      (node (ref "CfBP3") (pin "2") (pinfunction "2_2") (pintype "passive"))
      (node (ref "RsBP3") (pin "2") (pinfunction "2_2") (pintype "passive"))
      (node (ref "STM32") (pin "69") (pinfunction "PA10_69") (pintype "bidirectional"))
    )
    (net (code "15") (name "/PA11_BP4") (class "Default")
      (node (ref "CfBP4") (pin "2") (pinfunction "2_2") (pintype "passive"))
      (node (ref "RsBP4") (pin "2") (pinfunction "2_2") (pintype "passive"))
      (node (ref "STM32") (pin "70") (pinfunction "PA11_70") (pintype "bidirectional"))
    )
    (net (code "16") (name "/PA12_BP5") (class "Default")
      (node (ref "CfBP5") (pin "2") (pinfunction "2_2") (pintype "passive"))
      (node (ref "RsBP5") (pin "2") (pinfunction "2_2") (pintype "passive"))
      (node (ref "STM32") (pin "71") (pinfunction "PA12_71") (pintype "bidirectional"))
    )
    (net (code "17") (name "/PB0_SW_LCD") (class "Default")
      (node (ref "CfSWlcd") (pin "2") (pinfunction "2_2") (pintype "passive"))
      (node (ref "RsSWlcd") (pin "2") (pinfunction "2_2") (pintype "passive"))
      (node (ref "STM32") (pin "35") (pinfunction "PB0_35") (pintype "bidirectional"))
    )
    (net (code "18") (name "/PB1_BP_OK") (class "Default")
      (node (ref "CfBPok") (pin "2") (pinfunction "2_2") (pintype "passive"))
      (node (ref "RsBPok") (pin "1") (pinfunction "1_1") (pintype "passive"))
      (node (ref "STM32") (pin "36") (pinfunction "PB1_36") (pintype "bidirectional"))
    )
    (net (code "19") (name "/PB2_BP_+") (class "Default")
      (node (ref "CfBP+") (pin "2") (pinfunction "2_2") (pintype "passive"))
      (node (ref "RsBP+") (pin "1") (pinfunction "1_1") (pintype "passive"))
      (node (ref "STM32") (pin "37") (pinfunction "PB2-BOOT1(PB2)_37") (pintype "bidirectional"))
    )
    (net (code "20") (name "/PB4_PB_-") (class "Default")
      (node (ref "CfBP-") (pin "2") (pinfunction "2_2") (pintype "passive"))
      (node (ref "RsBP-") (pin "1") (pinfunction "1_1") (pintype "passive"))
      (node (ref "STM32") (pin "90") (pinfunction "PB4(NJTRST)_90") (pintype "bidirectional"))
    )
    (net (code "21") (name "/PB5_BP_Set") (class "Default")
      (node (ref "CfBPSet") (pin "2") (pinfunction "2_2") (pintype "passive"))
      (node (ref "RsBPSet") (pin "1") (pinfunction "1_1") (pintype "passive"))
      (node (ref "STM32") (pin "91") (pinfunction "PB5_91") (pintype "bidirectional"))
    )
    (net (code "22") (name "/PB6_U1TX") (class "Default")
      (node (ref "STM32") (pin "92") (pinfunction "PB6_92") (pintype "bidirectional"))
      (node (ref "STR_RsU1tx") (pin "2") (pinfunction "2_2") (pintype "passive"))
    )
    (net (code "23") (name "/PB7_U1RX") (class "Default")
      (node (ref "STM32") (pin "93") (pinfunction "PB7_93") (pintype "bidirectional"))
      (node (ref "STR_Cu1rx") (pin "2") (pinfunction "2_2") (pintype "passive"))
      (node (ref "STR_RpuU1rx") (pin "1") (pinfunction "1_1") (pintype "passive"))
      (node (ref "STR_Rsu1rx") (pin "1") (pinfunction "1_1") (pintype "passive"))
    )
    (net (code "24") (name "/PB8_I_AM_READY") (class "Default")
      (node (ref "Rihm_ready") (pin "2") (pinfunction "2_2") (pintype "passive"))
      (node (ref "STM32") (pin "95") (pinfunction "PB8_95") (pintype "bidirectional"))
    )
    (net (code "25") (name "/PB9_LCD_Reset") (class "Default")
      (node (ref "LCD*") (pin "1") (pinfunction "/RES_1") (pintype "passive"))
      (node (ref "STM32") (pin "96") (pinfunction "PB9_96") (pintype "bidirectional"))
    )
    (net (code "26") (name "/PB10_LCD_SCL") (class "Default")
      (node (ref "STM32") (pin "47") (pinfunction "PB10_47") (pintype "bidirectional"))
      (node (ref "st_lcd_scl") (pin "3") (pinfunction "3_3") (pintype "passive"))
    )
    (net (code "27") (name "/PB11_LCD_SDA") (class "Default")
      (node (ref "STM32") (pin "48") (pinfunction "PB11_48") (pintype "bidirectional"))
      (node (ref "st_lcd_sda") (pin "3") (pinfunction "3_3") (pintype "passive"))
    )
    (net (code "28") (name "/PB12_SPI_CS") (class "Default")
      (node (ref "SPI") (pin "4") (pinfunction "CS_4") (pintype "passive"))
      (node (ref "STM32") (pin "51") (pinfunction "PB12_51") (pintype "bidirectional"))
    )
    (net (code "29") (name "/PB13_SPI_SCK") (class "Default")
      (node (ref "SPI") (pin "5") (pinfunction "SCK_5") (pintype "passive"))
      (node (ref "STM32") (pin "52") (pinfunction "PB13_52") (pintype "bidirectional"))
    )
    (net (code "30") (name "/PB14_SPI_MISO") (class "Default")
      (node (ref "SPI") (pin "6") (pinfunction "MISO_6") (pintype "passive"))
      (node (ref "STM32") (pin "53") (pinfunction "PB14_53") (pintype "bidirectional"))
    )
    (net (code "31") (name "/PB15_SPI_MOSI") (class "Default")
      (node (ref "SPI") (pin "3") (pinfunction "MOSI_3") (pintype "passive"))
      (node (ref "STM32") (pin "54") (pinfunction "PB15_54") (pintype "bidirectional"))
    )
    (net (code "32") (name "/PC0_Meas_24Vperm") (class "Default")
      (node (ref "Cmes24") (pin "2") (pinfunction "2_2") (pintype "passive"))
      (node (ref "Rsme24") (pin "2") (pinfunction "2_2") (pintype "passive"))
      (node (ref "STM32") (pin "15") (pinfunction "PC0_15") (pintype "bidirectional"))
    )
    (net (code "33") (name "/PC1_SW16") (class "Default")
      (node (ref "CfSW16") (pin "2") (pinfunction "2_2") (pintype "passive"))
      (node (ref "RsSW16") (pin "2") (pinfunction "2_2") (pintype "passive"))
      (node (ref "STM32") (pin "16") (pinfunction "PC1_16") (pintype "bidirectional"))
    )
    (net (code "34") (name "/PC2_SW17") (class "Default")
      (node (ref "CfSW17") (pin "2") (pinfunction "2_2") (pintype "passive"))
      (node (ref "RsSW17") (pin "2") (pinfunction "2_2") (pintype "passive"))
      (node (ref "STM32") (pin "17") (pinfunction "PC2_17") (pintype "bidirectional"))
    )
    (net (code "35") (name "/PC3_SW18") (class "Default")
      (node (ref "CfSW18") (pin "2") (pinfunction "2_2") (pintype "passive"))
      (node (ref "RsSW18") (pin "2") (pinfunction "2_2") (pintype "passive"))
      (node (ref "STM32") (pin "18") (pinfunction "PC3_18") (pintype "bidirectional"))
    )
    (net (code "36") (name "/PC4_BP_RFU") (class "Default")
      (node (ref "CfBPrfu") (pin "2") (pinfunction "2_2") (pintype "passive"))
      (node (ref "RsBPrfu") (pin "2") (pinfunction "2_2") (pintype "passive"))
      (node (ref "STM32") (pin "33") (pinfunction "PC4_33") (pintype "bidirectional"))
    )
    (net (code "37") (name "/PC5_SW2") (class "Default")
      (node (ref "CfSW2") (pin "2") (pinfunction "2_2") (pintype "passive"))
      (node (ref "RsSW2") (pin "2") (pinfunction "2_2") (pintype "passive"))
      (node (ref "STM32") (pin "34") (pinfunction "PC5_34") (pintype "bidirectional"))
    )
    (net (code "38") (name "/PC6_LED_OK") (class "Default")
      (node (ref "RsLedOk") (pin "1") (pinfunction "1_1") (pintype "passive"))
      (node (ref "STM32") (pin "63") (pinfunction "PC6_63") (pintype "bidirectional"))
    )
    (net (code "39") (name "/PC7_LED_Set") (class "Default")
      (node (ref "RsLedSet") (pin "1") (pinfunction "1_1") (pintype "passive"))
      (node (ref "STM32") (pin "64") (pinfunction "PC7_64") (pintype "bidirectional"))
    )
    (net (code "40") (name "/PC8_LED_+") (class "Default")
      (node (ref "RsLed+") (pin "1") (pinfunction "1_1") (pintype "passive"))
      (node (ref "STM32") (pin "65") (pinfunction "PC8_65") (pintype "bidirectional"))
    )
    (net (code "41") (name "/PC9_LED_-") (class "Default")
      (node (ref "RsLed-") (pin "1") (pinfunction "1_1") (pintype "passive"))
      (node (ref "STM32") (pin "66") (pinfunction "PC9_66") (pintype "bidirectional"))
    )
    (net (code "42") (name "/PC13_WHO_AM_I") (class "Default")
      (node (ref "STM32") (pin "7") (pinfunction "PC13_7") (pintype "bidirectional"))
      (node (ref "STR_RdwnWAmI") (pin "2") (pinfunction "2_2") (pintype "passive"))
      (node (ref "STR_RupWAmI") (pin "1") (pinfunction "1_1") (pintype "passive"))
    )
    (net (code "43") (name "/PD0_CANRX") (class "Default")
      (node (ref "STM32") (pin "81") (pinfunction "PD0_81") (pintype "bidirectional"))
      (node (ref "STR_Ucan") (pin "4") (pinfunction "RXD_4") (pintype "output"))
    )
    (net (code "44") (name "/PD1_CANTX") (class "Default")
      (node (ref "STM32") (pin "82") (pinfunction "PD1_82") (pintype "bidirectional"))
      (node (ref "STR_Ucan") (pin "1") (pinfunction "TXD_1") (pintype "input"))
    )
    (net (code "45") (name "/PD2_LED_Green") (class "Default")
      (node (ref "RGreen") (pin "1") (pinfunction "1_1") (pintype "passive"))
      (node (ref "STM32") (pin "83") (pinfunction "PD2_83") (pintype "bidirectional"))
    )
    (net (code "46") (name "/PD3_LED_Red") (class "Default")
      (node (ref "Rred") (pin "1") (pinfunction "1_1") (pintype "passive"))
      (node (ref "STM32") (pin "84") (pinfunction "PD3_84") (pintype "bidirectional"))
    )
    (net (code "47") (name "/PD4_LED_Blue") (class "Default")
      (node (ref "RBlue") (pin "1") (pinfunction "1_1") (pintype "passive"))
      (node (ref "STM32") (pin "85") (pinfunction "PD4_85") (pintype "bidirectional"))
    )
    (net (code "48") (name "/PD6_SW_Color") (class "Default")
      (node (ref "CfSWcolor") (pin "2") (pinfunction "2_2") (pintype "passive"))
      (node (ref "RsSWcolor") (pin "2") (pinfunction "2_2") (pintype "passive"))
      (node (ref "STM32") (pin "87") (pinfunction "PD6_87") (pintype "bidirectional"))
    )
    (net (code "49") (name "/PD7_Biroute") (class "Default")
      (node (ref "CfBir") (pin "2") (pinfunction "2_2") (pintype "passive"))
      (node (ref "RsBir") (pin "2") (pinfunction "2_2") (pintype "passive"))
      (node (ref "STM32") (pin "88") (pinfunction "PD7_88") (pintype "bidirectional"))
    )
    (net (code "50") (name "/PD10_LED0") (class "Default")
      (node (ref "Rled0") (pin "2") (pinfunction "2_2") (pintype "passive"))
      (node (ref "STM32") (pin "57") (pinfunction "PD10_57") (pintype "bidirectional"))
    )
    (net (code "51") (name "/PD11_LED1") (class "Default")
      (node (ref "Rled1") (pin "2") (pinfunction "2_2") (pintype "passive"))
      (node (ref "STM32") (pin "58") (pinfunction "PD11_58") (pintype "bidirectional"))
    )
    (net (code "52") (name "/PD12_LED2") (class "Default")
      (node (ref "Rled2") (pin "2") (pinfunction "2_2") (pintype "passive"))
      (node (ref "STM32") (pin "59") (pinfunction "PD12_59") (pintype "bidirectional"))
    )
    (net (code "53") (name "/PD13_LED3") (class "Default")
      (node (ref "Rled3") (pin "2") (pinfunction "2_2") (pintype "passive"))
      (node (ref "STM32") (pin "60") (pinfunction "PD13_60") (pintype "bidirectional"))
    )
    (net (code "54") (name "/PD14_LED4") (class "Default")
      (node (ref "Rled4") (pin "2") (pinfunction "2_2") (pintype "passive"))
      (node (ref "STM32") (pin "61") (pinfunction "PD14_61") (pintype "bidirectional"))
    )
    (net (code "55") (name "/PD15_LED5") (class "Default")
      (node (ref "Rled5") (pin "2") (pinfunction "2_2") (pintype "passive"))
      (node (ref "STM32") (pin "62") (pinfunction "PD15_62") (pintype "bidirectional"))
    )
    (net (code "56") (name "/PE0_SW0") (class "Default")
      (node (ref "CfSW0") (pin "2") (pinfunction "2_2") (pintype "passive"))
      (node (ref "RsSW0") (pin "2") (pinfunction "2_2") (pintype "passive"))
      (node (ref "STM32") (pin "97") (pinfunction "PE0_97") (pintype "bidirectional"))
    )
    (net (code "57") (name "/PE1_SW1") (class "Default")
      (node (ref "CfSW1") (pin "2") (pinfunction "2_2") (pintype "passive"))
      (node (ref "RsSW1") (pin "2") (pinfunction "2_2") (pintype "passive"))
      (node (ref "STM32") (pin "98") (pinfunction "PE1_98") (pintype "bidirectional"))
    )
    (net (code "58") (name "/PE3_SW3") (class "Default")
      (node (ref "CfSW3") (pin "2") (pinfunction "2_2") (pintype "passive"))
      (node (ref "RsSW3") (pin "2") (pinfunction "2_2") (pintype "passive"))
      (node (ref "STM32") (pin "2") (pinfunction "PE3_2") (pintype "bidirectional"))
    )
    (net (code "59") (name "/PE4_SW4") (class "Default")
      (node (ref "CfSW4") (pin "2") (pinfunction "2_2") (pintype "passive"))
      (node (ref "RsSW4") (pin "2") (pinfunction "2_2") (pintype "passive"))
      (node (ref "STM32") (pin "3") (pinfunction "PE4_3") (pintype "bidirectional"))
    )
    (net (code "60") (name "/PE5_SW5") (class "Default")
      (node (ref "CfSW5") (pin "2") (pinfunction "2_2") (pintype "passive"))
      (node (ref "RsSW5") (pin "2") (pinfunction "2_2") (pintype "passive"))
      (node (ref "STM32") (pin "4") (pinfunction "PE5_4") (pintype "bidirectional"))
    )
    (net (code "61") (name "/PE6_SW6") (class "Default")
      (node (ref "CfSW6") (pin "2") (pinfunction "2_2") (pintype "passive"))
      (node (ref "RsSW6") (pin "2") (pinfunction "2_2") (pintype "passive"))
      (node (ref "STM32") (pin "5") (pinfunction "PE6_5") (pintype "bidirectional"))
    )
    (net (code "62") (name "/PE7_SW7") (class "Default")
      (node (ref "CfSW7") (pin "2") (pinfunction "2_2") (pintype "passive"))
      (node (ref "RsSW7") (pin "2") (pinfunction "2_2") (pintype "passive"))
      (node (ref "STM32") (pin "38") (pinfunction "PE7_38") (pintype "bidirectional"))
    )
    (net (code "63") (name "/PE8_SW8") (class "Default")
      (node (ref "CfSW8") (pin "2") (pinfunction "2_2") (pintype "passive"))
      (node (ref "RsSW8") (pin "2") (pinfunction "2_2") (pintype "passive"))
      (node (ref "STM32") (pin "39") (pinfunction "PE8_39") (pintype "bidirectional"))
    )
    (net (code "64") (name "/PE9_SW9") (class "Default")
      (node (ref "CfSW9") (pin "2") (pinfunction "2_2") (pintype "passive"))
      (node (ref "RsSW9") (pin "2") (pinfunction "2_2") (pintype "passive"))
      (node (ref "STM32") (pin "40") (pinfunction "PE9_40") (pintype "bidirectional"))
    )
    (net (code "65") (name "/PE10_SW10") (class "Default")
      (node (ref "CfSW10") (pin "2") (pinfunction "2_2") (pintype "passive"))
      (node (ref "RsSW10") (pin "2") (pinfunction "2_2") (pintype "passive"))
      (node (ref "STM32") (pin "41") (pinfunction "PE10_41") (pintype "bidirectional"))
    )
    (net (code "66") (name "/PE11_SW11") (class "Default")
      (node (ref "CfSW11") (pin "2") (pinfunction "2_2") (pintype "passive"))
      (node (ref "RsSW11") (pin "2") (pinfunction "2_2") (pintype "passive"))
      (node (ref "STM32") (pin "42") (pinfunction "PE11_42") (pintype "bidirectional"))
    )
    (net (code "67") (name "/PE12_SW12") (class "Default")
      (node (ref "CfSW12") (pin "2") (pinfunction "2_2") (pintype "passive"))
      (node (ref "RsSW12") (pin "2") (pinfunction "2_2") (pintype "passive"))
      (node (ref "STM32") (pin "43") (pinfunction "PE12_43") (pintype "bidirectional"))
    )
    (net (code "68") (name "/PE13_SW13") (class "Default")
      (node (ref "CfSW13") (pin "2") (pinfunction "2_2") (pintype "passive"))
      (node (ref "RsSW13") (pin "2") (pinfunction "2_2") (pintype "passive"))
      (node (ref "STM32") (pin "44") (pinfunction "PE13_44") (pintype "bidirectional"))
    )
    (net (code "69") (name "/PE14_SW14") (class "Default")
      (node (ref "CfSW14") (pin "2") (pinfunction "2_2") (pintype "passive"))
      (node (ref "RsSW14") (pin "2") (pinfunction "2_2") (pintype "passive"))
      (node (ref "STM32") (pin "45") (pinfunction "PE14_45") (pintype "bidirectional"))
    )
    (net (code "70") (name "/PE15_SW15") (class "Default")
      (node (ref "CfSW15") (pin "2") (pinfunction "2_2") (pintype "passive"))
      (node (ref "RsSW15") (pin "2") (pinfunction "2_2") (pintype "passive"))
      (node (ref "STM32") (pin "46") (pinfunction "PE15_46") (pintype "bidirectional"))
    )
    (net (code "71") (name "/PROG_NRST") (class "Default")
      (node (ref "Cnrst") (pin "2") (pinfunction "2_2") (pintype "passive"))
      (node (ref "P1") (pin "5") (pinfunction "NRST_5") (pintype "passive"))
      (node (ref "Rnrst") (pin "1") (pinfunction "1_1") (pintype "passive"))
      (node (ref "STM32") (pin "14") (pinfunction "NRST_14") (pintype "bidirectional"))
    )
    (net (code "72") (name "/PROG_SWCLK") (class "Default")
      (node (ref "P1") (pin "2") (pinfunction "SWCLK_2") (pintype "passive"))
      (node (ref "STM32") (pin "76") (pinfunction "PA14(JTCK-SWCLK)_76") (pintype "bidirectional"))
    )
    (net (code "73") (name "/PROG_SWDIO") (class "Default")
      (node (ref "P1") (pin "4") (pinfunction "SWDIO_4") (pintype "passive"))
      (node (ref "STM32") (pin "72") (pinfunction "PA13(JTMS-SWDIO)_72") (pintype "bidirectional"))
    )
    (net (code "74") (name "/PROG_SWO") (class "Default")
      (node (ref "P1") (pin "6") (pinfunction "SWO_6") (pintype "passive"))
      (node (ref "STM32") (pin "89") (pinfunction "PB3(JTDO/TRACESWO)_89") (pintype "bidirectional"))
    )
    (net (code "75") (name "/STR_LCD_SCL") (class "Default")
      (node (ref "FdP") (pin "14") (pinfunction "14_14") (pintype "passive"))
      (node (ref "st_lcd_scl") (pin "1") (pinfunction "1_1") (pintype "passive"))
    )
    (net (code "76") (name "/STR_LCD_SDA") (class "Default")
      (node (ref "FdP") (pin "7") (pinfunction "7_7") (pintype "passive"))
      (node (ref "st_lcd_sda") (pin "1") (pinfunction "1_1") (pintype "passive"))
    )
    (net (code "77") (name "/STR_PA2_XBEE_TX") (class "Default")
      (node (ref "FdP") (pin "5") (pinfunction "5_5") (pintype "passive"))
      (node (ref "YAHOURT") (pin "5") (pinfunction "5_5") (pintype "passive"))
    )
    (net (code "78") (name "/STR_PA3_XBEE_RX") (class "Default")
      (node (ref "FdP") (pin "6") (pinfunction "6_6") (pintype "passive"))
      (node (ref "YAHOURT") (pin "6") (pinfunction "6_6") (pintype "passive"))
    )
    (net (code "79") (name "/STR_PA5_RF_XBEE_RESET") (class "Default")
      (node (ref "FdP") (pin "10") (pinfunction "10_10") (pintype "passive"))
      (node (ref "FdP") (pin "8") (pinfunction "8_8") (pintype "passive"))
      (node (ref "YAHOURT") (pin "10") (pinfunction "10_10") (pintype "passive"))
      (node (ref "YAHOURT") (pin "8") (pinfunction "8_8") (pintype "passive"))
    )
    (net (code "80") (name "/STR_PA6_RF_Config") (class "Default")
      (node (ref "FdP") (pin "11") (pinfunction "11_11") (pintype "passive"))
      (node (ref "YAHOURT") (pin "11") (pinfunction "11_11") (pintype "passive"))
    )
    (net (code "81") (name "/STR_PC8_SynchroBalise") (class "Default")
      (node (ref "FdP") (pin "13") (pinfunction "13_13") (pintype "passive"))
      (node (ref "YAHOURT") (pin "13") (pinfunction "13_13") (pintype "passive"))
    )
    (net (code "82") (name "/STR_PD8_RF_TX") (class "Default")
      (node (ref "FdP") (pin "9") (pinfunction "9_9") (pintype "passive"))
      (node (ref "YAHOURT") (pin "9") (pinfunction "9_9") (pintype "passive"))
    )
    (net (code "83") (name "/STR_PD9_RF_RX") (class "Default")
      (node (ref "FdP") (pin "12") (pinfunction "12_12") (pintype "passive"))
      (node (ref "YAHOURT") (pin "12") (pinfunction "12_12") (pintype "passive"))
    )
    (net (code "84") (name "3V3") (class "Default")
      (node (ref "Cd0") (pin "2") (pinfunction "2_2") (pintype "passive"))
      (node (ref "Cd1") (pin "2") (pinfunction "2_2") (pintype "passive"))
      (node (ref "Cd2") (pin "2") (pinfunction "2_2") (pintype "passive"))
      (node (ref "Cd3") (pin "2") (pinfunction "2_2") (pintype "passive"))
      (node (ref "Cd3V_1") (pin "2") (pinfunction "2_2") (pintype "passive"))
      (node (ref "Cd4") (pin "2") (pinfunction "2_2") (pintype "passive"))
      (node (ref "Cd5") (pin "2") (pinfunction "2_2") (pintype "passive"))
      (node (ref "Cd6") (pin "2") (pinfunction "2_2") (pintype "passive"))
      (node (ref "Cd7") (pin "2") (pinfunction "2_2") (pintype "passive"))
      (node (ref "Cd8") (pin "2") (pinfunction "2_2") (pintype "passive"))
      (node (ref "Cd9") (pin "2") (pinfunction "2_2") (pintype "passive"))
      (node (ref "P1") (pin "1") (pinfunction "Vdd_Target_1") (pintype "passive"))
      (node (ref "Rnrst") (pin "2") (pinfunction "2_2") (pintype "passive"))
      (node (ref "RpuBP+") (pin "2") (pinfunction "2_2") (pintype "passive"))
      (node (ref "RpuBP-") (pin "2") (pinfunction "2_2") (pintype "passive"))
      (node (ref "RpuBP0") (pin "2") (pinfunction "2_2") (pintype "passive"))
      (node (ref "RpuBP1") (pin "2") (pinfunction "2_2") (pintype "passive"))
      (node (ref "RpuBP2") (pin "2") (pinfunction "2_2") (pintype "passive"))
      (node (ref "RpuBP3") (pin "2") (pinfunction "2_2") (pintype "passive"))
      (node (ref "RpuBP4") (pin "2") (pinfunction "2_2") (pintype "passive"))
      (node (ref "RpuBP5") (pin "2") (pinfunction "2_2") (pintype "passive"))
      (node (ref "RpuBPSet") (pin "2") (pinfunction "2_2") (pintype "passive"))
      (node (ref "RpuBPc") (pin "2") (pinfunction "2_2") (pintype "passive"))
      (node (ref "RpuBPok") (pin "2") (pinfunction "2_2") (pintype "passive"))
      (node (ref "RpuBPpm") (pin "2") (pinfunction "2_2") (pintype "passive"))
      (node (ref "RpuBPrfu") (pin "2") (pinfunction "2_2") (pintype "passive"))
      (node (ref "RpuBPst") (pin "2") (pinfunction "2_2") (pintype "passive"))
      (node (ref "RpuSW0") (pin "2") (pinfunction "2_2") (pintype "passive"))
      (node (ref "RpuSW1") (pin "2") (pinfunction "2_2") (pintype "passive"))
      (node (ref "RpuSW10") (pin "2") (pinfunction "2_2") (pintype "passive"))
      (node (ref "RpuSW11") (pin "2") (pinfunction "2_2") (pintype "passive"))
      (node (ref "RpuSW12") (pin "2") (pinfunction "2_2") (pintype "passive"))
      (node (ref "RpuSW13") (pin "2") (pinfunction "2_2") (pintype "passive"))
      (node (ref "RpuSW14") (pin "2") (pinfunction "2_2") (pintype "passive"))
      (node (ref "RpuSW15") (pin "2") (pinfunction "2_2") (pintype "passive"))
      (node (ref "RpuSW16") (pin "2") (pinfunction "2_2") (pintype "passive"))
      (node (ref "RpuSW17") (pin "2") (pinfunction "2_2") (pintype "passive"))
      (node (ref "RpuSW18") (pin "2") (pinfunction "2_2") (pintype "passive"))
      (node (ref "RpuSW2") (pin "2") (pinfunction "2_2") (pintype "passive"))
      (node (ref "RpuSW3") (pin "2") (pinfunction "2_2") (pintype "passive"))
      (node (ref "RpuSW4") (pin "2") (pinfunction "2_2") (pintype "passive"))
      (node (ref "RpuSW5") (pin "2") (pinfunction "2_2") (pintype "passive"))
      (node (ref "RpuSW6") (pin "2") (pinfunction "2_2") (pintype "passive"))
      (node (ref "RpuSW7") (pin "2") (pinfunction "2_2") (pintype "passive"))
      (node (ref "RpuSW8") (pin "2") (pinfunction "2_2") (pintype "passive"))
      (node (ref "RpuSW9") (pin "2") (pinfunction "2_2") (pintype "passive"))
      (node (ref "RpuSWcolor") (pin "2") (pinfunction "2_2") (pintype "passive"))
      (node (ref "RpuSWlcd") (pin "2") (pinfunction "2_2") (pintype "passive"))
      (node (ref "STM32") (pin "100") (pinfunction "VDD_100") (pintype "power_in"))
      (node (ref "STM32") (pin "11") (pinfunction "VDD_11") (pintype "power_in"))
      (node (ref "STM32") (pin "19") (pinfunction "VDD_19") (pintype "power_in"))
      (node (ref "STM32") (pin "21") (pinfunction "VREF+_21") (pintype "power_in"))
      (node (ref "STM32") (pin "22") (pinfunction "VDDA_22") (pintype "power_in"))
      (node (ref "STM32") (pin "28") (pinfunction "VDD_28") (pintype "power_in"))
      (node (ref "STM32") (pin "50") (pinfunction "VDD_50") (pintype "power_in"))
      (node (ref "STM32") (pin "6") (pinfunction "VBAT_6") (pintype "power_in"))
      (node (ref "STM32") (pin "75") (pinfunction "VDD_75") (pintype "power_in"))
      (node (ref "STR_RpuU1rx") (pin "2") (pinfunction "2_2") (pintype "passive"))
      (node (ref "STR_RpuU1tx") (pin "2") (pinfunction "2_2") (pintype "passive"))
      (node (ref "STR_RupWAmI") (pin "2") (pinfunction "2_2") (pintype "passive"))
      (node (ref "Ureg_3V") (pin "3") (pinfunction "VOUT_3") (pintype "power_in"))
      (node (ref "YAHOURT") (pin "3") (pinfunction "3_3") (pintype "passive"))
    )
    (net (code "85") (name "5V") (class "Default")
      (node (ref "Cde_out") (pin "1") (pinfunction "1_1") (pintype "passive"))
      (node (ref "Cdlcd") (pin "1") (pinfunction "1_1") (pintype "passive"))
      (node (ref "FdP_pwr") (pin "5") (pinfunction "5_5") (pintype "passive"))
      (node (ref "LCD*") (pin "10") (pinfunction "VDDIO_10") (pintype "passive"))
      (node (ref "LCD*") (pin "8") (pinfunction "VDD_8") (pintype "passive"))
      (node (ref "LED_color") (pin "1") (pinfunction "A_1") (pintype "passive"))
      (node (ref "Rcde") (pin "1") (pinfunction "1_1") (pintype "passive"))
      (node (ref "RledBir") (pin "2") (pinfunction "2_2") (pintype "passive"))
      (node (ref "RpuBir") (pin "2") (pinfunction "2_2") (pintype "passive"))
      (node (ref "RpuSCL") (pin "2") (pinfunction "2_2") (pintype "passive"))
      (node (ref "RpuSDA") (pin "2") (pinfunction "2_2") (pintype "passive"))
      (node (ref "Rretro") (pin "2") (pinfunction "2_2") (pintype "passive"))
      (node (ref "RsLedBP0") (pin "2") (pinfunction "2_2") (pintype "passive"))
      (node (ref "RsLedBP1") (pin "2") (pinfunction "2_2") (pintype "passive"))
      (node (ref "RsLedBP2") (pin "2") (pinfunction "2_2") (pintype "passive"))
      (node (ref "RsLedBP3") (pin "2") (pinfunction "2_2") (pintype "passive"))
      (node (ref "RsLedBP4") (pin "2") (pinfunction "2_2") (pintype "passive"))
      (node (ref "RsLedBP5") (pin "2") (pinfunction "2_2") (pintype "passive"))
      (node (ref "RsLedBPc") (pin "2") (pinfunction "2_2") (pintype "passive"))
      (node (ref "RsLedBPpm") (pin "2") (pinfunction "2_2") (pintype "passive"))
      (node (ref "RsLedBPrfu") (pin "2") (pinfunction "2_2") (pintype "passive"))
      (node (ref "RsLedBPst") (pin "2") (pinfunction "2_2") (pintype "passive"))
      (node (ref "SPI") (pin "1") (pinfunction "VDD_1") (pintype "passive"))
      (node (ref "STR_CdCan1") (pin "2") (pinfunction "2_2") (pintype "passive"))
      (node (ref "STR_CdCan2") (pin "2") (pinfunction "2_2") (pintype "passive"))
      (node (ref "STR_Ucan") (pin "3") (pinfunction "VDD_3") (pintype "power_in"))
      (node (ref "Ureg_3V") (pin "1") (pinfunction "VIN_1") (pintype "power_in"))
      (node (ref "YAHOURT") (pin "2") (pinfunction "2_2") (pintype "passive"))
    )
    (net (code "86") (name "5VPerm") (class "Default")
      (node (ref "CdPerm") (pin "2") (pinfunction "2_2") (pintype "passive"))
      (node (ref "Cde_in") (pin "1") (pinfunction "1_1") (pintype "passive"))
      (node (ref "FdP_pwr") (pin "4") (pinfunction "4_4") (pintype "passive"))
      (node (ref "TR_5V") (pin "3") (pinfunction "+Vout1_3") (pintype "passive"))
    )
    (net (code "87") (name "5V_STR") (class "Default")
      (node (ref "FdP") (pin "2") (pinfunction "2_2") (pintype "passive"))
    )
    (net (code "88") (name "12V") (class "Default")
      (node (ref "12V_out") (pin "1") (pinfunction "1_1") (pintype "passive"))
      (node (ref "F1") (pin "1") (pinfunction "1_1") (pintype "passive"))
    )
    (net (code "89") (name "12Vhok") (class "Default")
      (node (ref "12V_Hokuyo") (pin "2") (pinfunction "2_2") (pintype "passive"))
      (node (ref "Dtransil") (pin "2") (pinfunction "K_2") (pintype "passive"))
      (node (ref "F1") (pin "2") (pinfunction "2_2") (pintype "passive"))
      (node (ref "Rhok") (pin "1") (pinfunction "1_1") (pintype "passive"))
      (node (ref "Rmes12+") (pin "2") (pinfunction "2_2") (pintype "passive"))
    )
    (net (code "90") (name "12Vin") (class "Default")
      (node (ref "12V_FdP") (pin "2") (pinfunction "2_2") (pintype "passive"))
      (node (ref "12V_in") (pin "1") (pinfunction "1_1") (pintype "passive"))
    )
    (net (code "91") (name "24VPsce") (class "Default")
      (node (ref "24V_T12") (pin "1") (pinfunction "1_1") (pintype "passive"))
      (node (ref "ARU_out") (pin "1") (pinfunction "1_1") (pintype "passive"))
      (node (ref "FdP_pwr") (pin "2") (pinfunction "2_2") (pintype "passive"))
      (node (ref "J11_24V") (pin "2") (pinfunction "2_2") (pintype "passive"))
      (node (ref "J14_24V") (pin "2") (pinfunction "2_2") (pintype "passive"))
      (node (ref "J5_24V") (pin "2") (pinfunction "2_2") (pintype "passive"))
      (node (ref "R24Psce") (pin "1") (pinfunction "1_1") (pintype "passive"))
      (node (ref "Rmes24p+") (pin "2") (pinfunction "2_2") (pintype "passive"))
    )
    (net (code "92") (name "24Vcordon") (class "Default")
      (node (ref "CORDON_24V") (pin "1") (pinfunction "1_1") (pintype "passive"))
      (node (ref "Dcordon") (pin "1") (pinfunction "A1_1") (pintype "passive"))
      (node (ref "Dcordon") (pin "3") (pinfunction "A2_3") (pintype "passive"))
    )
    (net (code "93") (name "24Vperm") (class "Default")
      (node (ref "ARU_in") (pin "1") (pinfunction "1_1") (pintype "passive"))
      (node (ref "BAT_24V") (pin "1") (pinfunction "1_1") (pintype "passive"))
      (node (ref "Batterie") (pin "2") (pinfunction "2_2") (pintype "passive"))
      (node (ref "CORDON_CHARGE") (pin "1") (pinfunction "1_1") (pintype "passive"))
      (node (ref "Chargeur") (pin "2") (pinfunction "2_2") (pintype "passive"))
      (node (ref "Dcordon") (pin "2") (pinfunction "K_2") (pintype "passive"))
      (node (ref "Dreverse") (pin "1") (pinfunction "A1_1") (pintype "passive"))
      (node (ref "Dreverse") (pin "3") (pinfunction "A2_3") (pintype "passive"))
      (node (ref "R24in") (pin "1") (pinfunction "1_1") (pintype "passive"))
      (node (ref "Rmes24+") (pin "2") (pinfunction "2_2") (pintype "passive"))
    )
    (net (code "94") (name "GND") (class "Default")
      (node (ref "BP0") (pin "3") (pinfunction "3_3") (pintype "passive"))
      (node (ref "BP0") (pin "4") (pinfunction "4_4") (pintype "passive"))
      (node (ref "BP0") (pin "6") (pinfunction "-_6") (pintype "passive"))
      (node (ref "BP1") (pin "3") (pinfunction "3_3") (pintype "passive"))
      (node (ref "BP1") (pin "4") (pinfunction "4_4") (pintype "passive"))
      (node (ref "BP1") (pin "6") (pinfunction "-_6") (pintype "passive"))
      (node (ref "BP2") (pin "3") (pinfunction "3_3") (pintype "passive"))
      (node (ref "BP2") (pin "4") (pinfunction "4_4") (pintype "passive"))
      (node (ref "BP2") (pin "6") (pinfunction "-_6") (pintype "passive"))
      (node (ref "BP3") (pin "3") (pinfunction "3_3") (pintype "passive"))
      (node (ref "BP3") (pin "4") (pinfunction "4_4") (pintype "passive"))
      (node (ref "BP3") (pin "6") (pinfunction "-_6") (pintype "passive"))
      (node (ref "BP4") (pin "3") (pinfunction "3_3") (pintype "passive"))
      (node (ref "BP4") (pin "4") (pinfunction "4_4") (pintype "passive"))
      (node (ref "BP4") (pin "6") (pinfunction "-_6") (pintype "passive"))
      (node (ref "BP5") (pin "3") (pinfunction "3_3") (pintype "passive"))
      (node (ref "BP5") (pin "4") (pinfunction "4_4") (pintype "passive"))
      (node (ref "BP5") (pin "6") (pinfunction "-_6") (pintype "passive"))
      (node (ref "BP_LCD+") (pin "3") (pinfunction "3_3") (pintype "passive"))
      (node (ref "BP_LCD+") (pin "4") (pinfunction "4_4") (pintype "passive"))
      (node (ref "BP_LCD+") (pin "6") (pinfunction "-_6") (pintype "passive"))
      (node (ref "BP_LCD-") (pin "3") (pinfunction "3_3") (pintype "passive"))
      (node (ref "BP_LCD-") (pin "4") (pinfunction "4_4") (pintype "passive"))
      (node (ref "BP_LCD-") (pin "6") (pinfunction "-_6") (pintype "passive"))
      (node (ref "BP_LCD_OK") (pin "3") (pinfunction "3_3") (pintype "passive"))
      (node (ref "BP_LCD_OK") (pin "4") (pinfunction "4_4") (pintype "passive"))
      (node (ref "BP_LCD_OK") (pin "6") (pinfunction "-_6") (pintype "passive"))
      (node (ref "BP_Set") (pin "3") (pinfunction "3_3") (pintype "passive"))
      (node (ref "BP_Set") (pin "4") (pinfunction "4_4") (pintype "passive"))
      (node (ref "BP_Set") (pin "6") (pinfunction "-_6") (pintype "passive"))
      (node (ref "BPc") (pin "3") (pinfunction "3_3") (pintype "passive"))
      (node (ref "BPc") (pin "4") (pinfunction "4_4") (pintype "passive"))
      (node (ref "BPc") (pin "6") (pinfunction "-_6") (pintype "passive"))
      (node (ref "BPpm") (pin "3") (pinfunction "3_3") (pintype "passive"))
      (node (ref "BPpm") (pin "4") (pinfunction "4_4") (pintype "passive"))
      (node (ref "BPpm") (pin "6") (pinfunction "-_6") (pintype "passive"))
      (node (ref "BPrfu") (pin "3") (pinfunction "3_3") (pintype "passive"))
      (node (ref "BPrfu") (pin "4") (pinfunction "4_4") (pintype "passive"))
      (node (ref "BPrfu") (pin "6") (pinfunction "-_6") (pintype "passive"))
      (node (ref "BPst") (pin "3") (pinfunction "3_3") (pintype "passive"))
      (node (ref "BPst") (pin "4") (pinfunction "4_4") (pintype "passive"))
      (node (ref "BPst") (pin "6") (pinfunction "-_6") (pintype "passive"))
      (node (ref "C46") (pin "1") (pinfunction "1_1") (pintype "passive"))
      (node (ref "C47") (pin "1") (pinfunction "1_1") (pintype "passive"))
      (node (ref "C49") (pin "1") (pinfunction "1_1") (pintype "passive"))
      (node (ref "C50") (pin "1") (pinfunction "1_1") (pintype "passive"))
      (node (ref "CV0") (pin "2") (pinfunction "2_2") (pintype "passive"))
      (node (ref "CV1") (pin "2") (pinfunction "2_2") (pintype "passive"))
      (node (ref "CV2") (pin "2") (pinfunction "2_2") (pintype "passive"))
      (node (ref "CV3") (pin "2") (pinfunction "2_2") (pintype "passive"))
      (node (ref "CV4") (pin "2") (pinfunction "2_2") (pintype "passive"))
      (node (ref "CVOUT") (pin "2") (pinfunction "2_2") (pintype "passive"))
      (node (ref "Cd0") (pin "1") (pinfunction "1_1") (pintype "passive"))
      (node (ref "Cd1") (pin "1") (pinfunction "1_1") (pintype "passive"))
      (node (ref "Cd2") (pin "1") (pinfunction "1_1") (pintype "passive"))
      (node (ref "Cd3") (pin "1") (pinfunction "1_1") (pintype "passive"))
      (node (ref "Cd3V_1") (pin "1") (pinfunction "1_1") (pintype "passive"))
      (node (ref "Cd4") (pin "1") (pinfunction "1_1") (pintype "passive"))
      (node (ref "Cd5") (pin "1") (pinfunction "1_1") (pintype "passive"))
      (node (ref "Cd6") (pin "1") (pinfunction "1_1") (pintype "passive"))
      (node (ref "Cd7") (pin "1") (pinfunction "1_1") (pintype "passive"))
      (node (ref "Cd8") (pin "1") (pinfunction "1_1") (pintype "passive"))
      (node (ref "Cd9") (pin "1") (pinfunction "1_1") (pintype "passive"))
      (node (ref "CdPerm") (pin "1") (pinfunction "1_1") (pintype "passive"))
      (node (ref "Cdlcd") (pin "2") (pinfunction "2_2") (pintype "passive"))
      (node (ref "CfBP+") (pin "1") (pinfunction "1_1") (pintype "passive"))
      (node (ref "CfBP-") (pin "1") (pinfunction "1_1") (pintype "passive"))
      (node (ref "CfBP0") (pin "1") (pinfunction "1_1") (pintype "passive"))
      (node (ref "CfBP1") (pin "1") (pinfunction "1_1") (pintype "passive"))
      (node (ref "CfBP2") (pin "1") (pinfunction "1_1") (pintype "passive"))
      (node (ref "CfBP3") (pin "1") (pinfunction "1_1") (pintype "passive"))
      (node (ref "CfBP4") (pin "1") (pinfunction "1_1") (pintype "passive"))
      (node (ref "CfBP5") (pin "1") (pinfunction "1_1") (pintype "passive"))
      (node (ref "CfBPSet") (pin "1") (pinfunction "1_1") (pintype "passive"))
      (node (ref "CfBPc") (pin "1") (pinfunction "1_1") (pintype "passive"))
      (node (ref "CfBPok") (pin "1") (pinfunction "1_1") (pintype "passive"))
      (node (ref "CfBPpm") (pin "1") (pinfunction "1_1") (pintype "passive"))
      (node (ref "CfBPrfu") (pin "1") (pinfunction "1_1") (pintype "passive"))
      (node (ref "CfBPst") (pin "1") (pinfunction "1_1") (pintype "passive"))
      (node (ref "CfBir") (pin "1") (pinfunction "1_1") (pintype "passive"))
      (node (ref "CfSW0") (pin "1") (pinfunction "1_1") (pintype "passive"))
      (node (ref "CfSW1") (pin "1") (pinfunction "1_1") (pintype "passive"))
      (node (ref "CfSW10") (pin "1") (pinfunction "1_1") (pintype "passive"))
      (node (ref "CfSW11") (pin "1") (pinfunction "1_1") (pintype "passive"))
      (node (ref "CfSW12") (pin "1") (pinfunction "1_1") (pintype "passive"))
      (node (ref "CfSW13") (pin "1") (pinfunction "1_1") (pintype "passive"))
      (node (ref "CfSW14") (pin "1") (pinfunction "1_1") (pintype "passive"))
      (node (ref "CfSW15") (pin "1") (pinfunction "1_1") (pintype "passive"))
      (node (ref "CfSW16") (pin "1") (pinfunction "1_1") (pintype "passive"))
      (node (ref "CfSW17") (pin "1") (pinfunction "1_1") (pintype "passive"))
      (node (ref "CfSW18") (pin "1") (pinfunction "1_1") (pintype "passive"))
      (node (ref "CfSW2") (pin "1") (pinfunction "1_1") (pintype "passive"))
      (node (ref "CfSW3") (pin "1") (pinfunction "1_1") (pintype "passive"))
      (node (ref "CfSW4") (pin "1") (pinfunction "1_1") (pintype "passive"))
      (node (ref "CfSW5") (pin "1") (pinfunction "1_1") (pintype "passive"))
      (node (ref "CfSW6") (pin "1") (pinfunction "1_1") (pintype "passive"))
      (node (ref "CfSW7") (pin "1") (pinfunction "1_1") (pintype "passive"))
      (node (ref "CfSW8") (pin "1") (pinfunction "1_1") (pintype "passive"))
      (node (ref "CfSW9") (pin "1") (pinfunction "1_1") (pintype "passive"))
      (node (ref "CfSWcolor") (pin "1") (pinfunction "1_1") (pintype "passive"))
      (node (ref "CfSWlcd") (pin "1") (pinfunction "1_1") (pintype "passive"))
      (node (ref "Cmes12") (pin "1") (pinfunction "1_1") (pintype "passive"))
      (node (ref "Cmes24") (pin "1") (pinfunction "1_1") (pintype "passive"))
      (node (ref "Cmes24p") (pin "1") (pinfunction "1_1") (pintype "passive"))
      (node (ref "Cnrst") (pin "1") (pinfunction "1_1") (pintype "passive"))
      (node (ref "Dcde") (pin "2") (pinfunction "K_2") (pintype "passive"))
      (node (ref "FdP") (pin "1") (pinfunction "1_1") (pintype "passive"))
      (node (ref "FdP") (pin "4") (pinfunction "4_4") (pintype "passive"))
      (node (ref "FdP_pwr") (pin "3") (pinfunction "3_3") (pintype "passive"))
      (node (ref "LCD*") (pin "11") (pinfunction "VSS_11") (pintype "passive"))
      (node (ref "LCD*") (pin "9") (pinfunction "VDDREG_9") (pintype "passive"))
      (node (ref "LCD*") (pin "K") (pinfunction "K_K") (pintype "passive"))
      (node (ref "Led0") (pin "2") (pinfunction "K_2") (pintype "passive"))
      (node (ref "Led1") (pin "2") (pinfunction "K_2") (pintype "passive"))
      (node (ref "Led2") (pin "2") (pinfunction "K_2") (pintype "passive"))
      (node (ref "Led3") (pin "2") (pinfunction "K_2") (pintype "passive"))
      (node (ref "Led4") (pin "2") (pinfunction "K_2") (pintype "passive"))
      (node (ref "Led5") (pin "2") (pinfunction "K_2") (pintype "passive"))
      (node (ref "P1") (pin "3") (pinfunction "GND_3") (pintype "passive"))
      (node (ref "Rmes12-") (pin "1") (pinfunction "1_1") (pintype "passive"))
      (node (ref "Rmes24-") (pin "1") (pinfunction "1_1") (pintype "passive"))
      (node (ref "Rmes24p-") (pin "1") (pinfunction "1_1") (pintype "passive"))
      (node (ref "SPI") (pin "2") (pinfunction "GND_2") (pintype "passive"))
      (node (ref "STM32") (pin "10") (pinfunction "VSS_10") (pintype "power_in"))
      (node (ref "STM32") (pin "20") (pinfunction "VSSA_20") (pintype "power_in"))
      (node (ref "STM32") (pin "27") (pinfunction "VSS_27") (pintype "power_in"))
      (node (ref "STM32") (pin "74") (pinfunction "VSS_74") (pintype "power_in"))
      (node (ref "STM32") (pin "94") (pinfunction "BOOT0_94") (pintype "input"))
      (node (ref "STM32") (pin "99") (pinfunction "VSS_99") (pintype "power_in"))
      (node (ref "STR_CdCan1") (pin "1") (pinfunction "1_1") (pintype "passive"))
      (node (ref "STR_CdCan2") (pin "1") (pinfunction "1_1") (pintype "passive"))
      (node (ref "STR_Cu1rx") (pin "1") (pinfunction "1_1") (pintype "passive"))
      (node (ref "STR_RdwnWAmI") (pin "1") (pinfunction "1_1") (pintype "passive"))
      (node (ref "STR_UART1") (pin "5") (pinfunction "5_5") (pintype "passive"))
      (node (ref "STR_UART1") (pin "6") (pinfunction "6_6") (pintype "passive"))
      (node (ref "STR_Ucan") (pin "2") (pinfunction "VSS_2") (pintype "power_in"))
      (node (ref "STR_Ucan") (pin "8") (pinfunction "RS_8") (pintype "input"))
      (node (ref "STgnd") (pin "2") (pinfunction "2_2") (pintype "passive"))
      (node (ref "SW0") (pin "COMMON1") (pinfunction "COMMON1_COMMON1") (pintype "passive"))
      (node (ref "SW1") (pin "COMMON1") (pinfunction "COMMON1_COMMON1") (pintype "passive"))
      (node (ref "SW10") (pin "COMMON1") (pinfunction "COMMON1_COMMON1") (pintype "passive"))
      (node (ref "SW11") (pin "COMMON1") (pinfunction "COMMON1_COMMON1") (pintype "passive"))
      (node (ref "SW12") (pin "COMMON1") (pinfunction "COMMON1_COMMON1") (pintype "passive"))
      (node (ref "SW13") (pin "COMMON1") (pinfunction "COMMON1_COMMON1") (pintype "passive"))
      (node (ref "SW14") (pin "COMMON1") (pinfunction "COMMON1_COMMON1") (pintype "passive"))
      (node (ref "SW15") (pin "COMMON1") (pinfunction "COMMON1_COMMON1") (pintype "passive"))
      (node (ref "SW16") (pin "COMMON1") (pinfunction "COMMON1_COMMON1") (pintype "passive"))
      (node (ref "SW17") (pin "COMMON1") (pinfunction "COMMON1_COMMON1") (pintype "passive"))
      (node (ref "SW18") (pin "COMMON1") (pinfunction "COMMON1_COMMON1") (pintype "passive"))
      (node (ref "SW2") (pin "COMMON1") (pinfunction "COMMON1_COMMON1") (pintype "passive"))
      (node (ref "SW3") (pin "COMMON1") (pinfunction "COMMON1_COMMON1") (pintype "passive"))
      (node (ref "SW4") (pin "COMMON1") (pinfunction "COMMON1_COMMON1") (pintype "passive"))
      (node (ref "SW5") (pin "COMMON1") (pinfunction "COMMON1_COMMON1") (pintype "passive"))
      (node (ref "SW6") (pin "COMMON1") (pinfunction "COMMON1_COMMON1") (pintype "passive"))
      (node (ref "SW7") (pin "COMMON1") (pinfunction "COMMON1_COMMON1") (pintype "passive"))
      (node (ref "SW8") (pin "COMMON1") (pinfunction "COMMON1_COMMON1") (pintype "passive"))
      (node (ref "SW9") (pin "COMMON1") (pinfunction "COMMON1_COMMON1") (pintype "passive"))
      (node (ref "SWcolor") (pin "COMMON1") (pinfunction "COMMON1_COMMON1") (pintype "passive"))
      (node (ref "SWlcd") (pin "COMMON1") (pinfunction "COMMON1_COMMON1") (pintype "passive"))
      (node (ref "TR_5V") (pin "5") (pinfunction "-Vout1_5") (pintype "passive"))
      (node (ref "Ureg_3V") (pin "2") (pinfunction "GND_2") (pintype "power_in"))
      (node (ref "Ureg_3V") (pin "4") (pinfunction "GND_4") (pintype "power_in"))
      (node (ref "V1") (pin "1") (pinfunction "1_1") (pintype "passive"))
      (node (ref "V2") (pin "1") (pinfunction "1_1") (pintype "passive"))
      (node (ref "V3") (pin "1") (pinfunction "1_1") (pintype "passive"))
      (node (ref "V4") (pin "1") (pinfunction "1_1") (pintype "passive"))
      (node (ref "V5") (pin "1") (pinfunction "1_1") (pintype "passive"))
      (node (ref "V6") (pin "1") (pinfunction "1_1") (pintype "passive"))
      (node (ref "V7") (pin "1") (pinfunction "1_1") (pintype "passive"))
      (node (ref "V8") (pin "1") (pinfunction "1_1") (pintype "passive"))
      (node (ref "V9") (pin "1") (pinfunction "1_1") (pintype "passive"))
      (node (ref "YAHOURT") (pin "1") (pinfunction "1_1") (pintype "passive"))
      (node (ref "YAHOURT") (pin "4") (pinfunction "4_4") (pintype "passive"))
      (node (ref "biroute_gnd") (pin "1") (pinfunction "1_1") (pintype "passive"))
    )
    (net (code "95") (name "GND_12") (class "Default")
      (node (ref "12V_FdP") (pin "1") (pinfunction "1_1") (pintype "passive"))
      (node (ref "12V_Hokuyo") (pin "1") (pinfunction "1_1") (pintype "passive"))
      (node (ref "Dhok") (pin "2") (pinfunction "K_2") (pintype "passive"))
      (node (ref "Dtransil") (pin "1") (pinfunction "A_1") (pintype "passive"))
    )
    (net (code "96") (name "GND_24") (class "Default")
      (node (ref "BAT_GND") (pin "1") (pinfunction "1_1") (pintype "passive"))
      (node (ref "Batterie") (pin "1") (pinfunction "1_1") (pintype "passive"))
      (node (ref "CORDON_GND") (pin "1") (pinfunction "1_1") (pintype "passive"))
      (node (ref "Cd24VCDE") (pin "1") (pinfunction "1_1") (pintype "passive"))
      (node (ref "Chargeur") (pin "1") (pinfunction "1_1") (pintype "passive"))
      (node (ref "D24Psce") (pin "2") (pinfunction "K_2") (pintype "passive"))
      (node (ref "D24in") (pin "2") (pinfunction "K_2") (pintype "passive"))
      (node (ref "FdP_pwr") (pin "1") (pinfunction "1_1") (pintype "passive"))
      (node (ref "GND_T12") (pin "1") (pinfunction "1_1") (pintype "passive"))
      (node (ref "J11_24V") (pin "1") (pinfunction "1_1") (pintype "passive"))
      (node (ref "J14_24V") (pin "1") (pinfunction "1_1") (pintype "passive"))
      (node (ref "J5_24V") (pin "1") (pinfunction "1_1") (pintype "passive"))
      (node (ref "STgnd") (pin "1") (pinfunction "1_1") (pintype "passive"))
      (node (ref "TR_5V") (pin "2") (pinfunction "-Vin_2") (pintype "passive"))
    )
    (net (code "97") (name "Net-(BP0-+)") (class "Default")
      (node (ref "BP0") (pin "5") (pinfunction "+_5") (pintype "passive"))
      (node (ref "RsLedBP0") (pin "1") (pinfunction "1_1") (pintype "passive"))
    )
    (net (code "98") (name "Net-(BP0-3-Pad2)") (class "Default")
      (node (ref "BP0") (pin "2") (pinfunction "3_2") (pintype "passive"))
      (node (ref "RpuBP0") (pin "1") (pinfunction "1_1") (pintype "passive"))
      (node (ref "RsBP0") (pin "1") (pinfunction "1_1") (pintype "passive"))
    )
    (net (code "99") (name "Net-(BP1-+)") (class "Default")
      (node (ref "BP1") (pin "5") (pinfunction "+_5") (pintype "passive"))
      (node (ref "RsLedBP1") (pin "1") (pinfunction "1_1") (pintype "passive"))
    )
    (net (code "100") (name "Net-(BP1-3-Pad2)") (class "Default")
      (node (ref "BP1") (pin "2") (pinfunction "3_2") (pintype "passive"))
      (node (ref "RpuBP1") (pin "1") (pinfunction "1_1") (pintype "passive"))
      (node (ref "RsBP1") (pin "1") (pinfunction "1_1") (pintype "passive"))
    )
    (net (code "101") (name "Net-(BP2-+)") (class "Default")
      (node (ref "BP2") (pin "5") (pinfunction "+_5") (pintype "passive"))
      (node (ref "RsLedBP2") (pin "1") (pinfunction "1_1") (pintype "passive"))
    )
    (net (code "102") (name "Net-(BP2-3-Pad2)") (class "Default")
      (node (ref "BP2") (pin "2") (pinfunction "3_2") (pintype "passive"))
      (node (ref "RpuBP2") (pin "1") (pinfunction "1_1") (pintype "passive"))
      (node (ref "RsBP2") (pin "1") (pinfunction "1_1") (pintype "passive"))
    )
    (net (code "103") (name "Net-(BP3-+)") (class "Default")
      (node (ref "BP3") (pin "5") (pinfunction "+_5") (pintype "passive"))
      (node (ref "RsLedBP3") (pin "1") (pinfunction "1_1") (pintype "passive"))
    )
    (net (code "104") (name "Net-(BP3-3-Pad2)") (class "Default")
      (node (ref "BP3") (pin "2") (pinfunction "3_2") (pintype "passive"))
      (node (ref "RpuBP3") (pin "1") (pinfunction "1_1") (pintype "passive"))
      (node (ref "RsBP3") (pin "1") (pinfunction "1_1") (pintype "passive"))
    )
    (net (code "105") (name "Net-(BP4-+)") (class "Default")
      (node (ref "BP4") (pin "5") (pinfunction "+_5") (pintype "passive"))
      (node (ref "RsLedBP4") (pin "1") (pinfunction "1_1") (pintype "passive"))
    )
    (net (code "106") (name "Net-(BP4-3-Pad2)") (class "Default")
      (node (ref "BP4") (pin "2") (pinfunction "3_2") (pintype "passive"))
      (node (ref "RpuBP4") (pin "1") (pinfunction "1_1") (pintype "passive"))
      (node (ref "RsBP4") (pin "1") (pinfunction "1_1") (pintype "passive"))
    )
    (net (code "107") (name "Net-(BP5-+)") (class "Default")
      (node (ref "BP5") (pin "5") (pinfunction "+_5") (pintype "passive"))
      (node (ref "RsLedBP5") (pin "1") (pinfunction "1_1") (pintype "passive"))
    )
    (net (code "108") (name "Net-(BP5-3-Pad2)") (class "Default")
      (node (ref "BP5") (pin "2") (pinfunction "3_2") (pintype "passive"))
      (node (ref "RpuBP5") (pin "1") (pinfunction "1_1") (pintype "passive"))
      (node (ref "RsBP5") (pin "1") (pinfunction "1_1") (pintype "passive"))
    )
    (net (code "109") (name "Net-(BP_LCD+-+)") (class "Default")
      (node (ref "BP_LCD+") (pin "5") (pinfunction "+_5") (pintype "passive"))
      (node (ref "RsLed+") (pin "2") (pinfunction "2_2") (pintype "passive"))
    )
    (net (code "110") (name "Net-(BP_LCD+-Pad1)") (class "Default")
      (node (ref "BP_LCD+") (pin "1") (pinfunction "1_1") (pintype "passive"))
      (node (ref "RpuBP+") (pin "1") (pinfunction "1_1") (pintype "passive"))
      (node (ref "RsBP+") (pin "2") (pinfunction "2_2") (pintype "passive"))
    )
    (net (code "111") (name "Net-(BP_LCD--+)") (class "Default")
      (node (ref "BP_LCD-") (pin "5") (pinfunction "+_5") (pintype "passive"))
      (node (ref "RsLed-") (pin "2") (pinfunction "2_2") (pintype "passive"))
    )
    (net (code "112") (name "Net-(BP_LCD--Pad1)") (class "Default")
      (node (ref "BP_LCD-") (pin "1") (pinfunction "1_1") (pintype "passive"))
      (node (ref "RpuBP-") (pin "1") (pinfunction "1_1") (pintype "passive"))
      (node (ref "RsBP-") (pin "2") (pinfunction "2_2") (pintype "passive"))
    )
    (net (code "113") (name "Net-(BP_LCD_OK-+)") (class "Default")
      (node (ref "BP_LCD_OK") (pin "5") (pinfunction "+_5") (pintype "passive"))
      (node (ref "RsLedOk") (pin "2") (pinfunction "2_2") (pintype "passive"))
    )
    (net (code "114") (name "Net-(BP_LCD_OK-Pad1)") (class "Default")
      (node (ref "BP_LCD_OK") (pin "1") (pinfunction "1_1") (pintype "passive"))
      (node (ref "RpuBPok") (pin "1") (pinfunction "1_1") (pintype "passive"))
      (node (ref "RsBPok") (pin "2") (pinfunction "2_2") (pintype "passive"))
    )
    (net (code "115") (name "Net-(BP_Set-+)") (class "Default")
      (node (ref "BP_Set") (pin "5") (pinfunction "+_5") (pintype "passive"))
      (node (ref "RsLedSet") (pin "2") (pinfunction "2_2") (pintype "passive"))
    )
    (net (code "116") (name "Net-(BP_Set-Pad1)") (class "Default")
      (node (ref "BP_Set") (pin "1") (pinfunction "1_1") (pintype "passive"))
      (node (ref "RpuBPSet") (pin "1") (pinfunction "1_1") (pintype "passive"))
      (node (ref "RsBPSet") (pin "2") (pinfunction "2_2") (pintype "passive"))
    )
    (net (code "117") (name "Net-(BPc-+)") (class "Default")
      (node (ref "BPc") (pin "5") (pinfunction "+_5") (pintype "passive"))
      (node (ref "RsLedBPc") (pin "1") (pinfunction "1_1") (pintype "passive"))
    )
    (net (code "118") (name "Net-(BPc-3-Pad2)") (class "Default")
      (node (ref "BPc") (pin "2") (pinfunction "3_2") (pintype "passive"))
      (node (ref "RpuBPc") (pin "1") (pinfunction "1_1") (pintype "passive"))
      (node (ref "RsBPc") (pin "1") (pinfunction "1_1") (pintype "passive"))
    )
    (net (code "119") (name "Net-(BPpm-+)") (class "Default")
      (node (ref "BPpm") (pin "5") (pinfunction "+_5") (pintype "passive"))
      (node (ref "RsLedBPpm") (pin "1") (pinfunction "1_1") (pintype "passive"))
    )
    (net (code "120") (name "Net-(BPpm-3-Pad2)") (class "Default")
      (node (ref "BPpm") (pin "2") (pinfunction "3_2") (pintype "passive"))
      (node (ref "RpuBPpm") (pin "1") (pinfunction "1_1") (pintype "passive"))
      (node (ref "RsBPpm") (pin "1") (pinfunction "1_1") (pintype "passive"))
    )
    (net (code "121") (name "Net-(BPrfu-+)") (class "Default")
      (node (ref "BPrfu") (pin "5") (pinfunction "+_5") (pintype "passive"))
      (node (ref "RsLedBPrfu") (pin "1") (pinfunction "1_1") (pintype "passive"))
    )
    (net (code "122") (name "Net-(BPrfu-3-Pad2)") (class "Default")
      (node (ref "BPrfu") (pin "2") (pinfunction "3_2") (pintype "passive"))
      (node (ref "RpuBPrfu") (pin "1") (pinfunction "1_1") (pintype "passive"))
      (node (ref "RsBPrfu") (pin "1") (pinfunction "1_1") (pintype "passive"))
    )
    (net (code "123") (name "Net-(BPst-+)") (class "Default")
      (node (ref "BPst") (pin "5") (pinfunction "+_5") (pintype "passive"))
      (node (ref "RsLedBPst") (pin "1") (pinfunction "1_1") (pintype "passive"))
    )
    (net (code "124") (name "Net-(BPst-3-Pad2)") (class "Default")
      (node (ref "BPst") (pin "2") (pinfunction "3_2") (pintype "passive"))
      (node (ref "RpuBPst") (pin "1") (pinfunction "1_1") (pintype "passive"))
      (node (ref "RsBPst") (pin "1") (pinfunction "1_1") (pintype "passive"))
    )
    (net (code "125") (name "Net-(D24Psce-A)") (class "Default")
      (node (ref "D24Psce") (pin "1") (pinfunction "A_1") (pintype "passive"))
      (node (ref "R24Psce") (pin "2") (pinfunction "2_2") (pintype "passive"))
    )
    (net (code "126") (name "Net-(D24in-A)") (class "Default")
      (node (ref "D24in") (pin "1") (pinfunction "A_1") (pintype "passive"))
      (node (ref "R24in") (pin "2") (pinfunction "2_2") (pintype "passive"))
    )
    (net (code "127") (name "Net-(Dcde-A)") (class "Default")
      (node (ref "Dcde") (pin "1") (pinfunction "A_1") (pintype "passive"))
      (node (ref "Rcde") (pin "2") (pinfunction "2_2") (pintype "passive"))
    )
    (net (code "128") (name "Net-(Dhok-A)") (class "Default")
      (node (ref "Dhok") (pin "1") (pinfunction "A_1") (pintype "passive"))
      (node (ref "Rhok") (pin "2") (pinfunction "2_2") (pintype "passive"))
    )
    (net (code "129") (name "Net-(Dreverse-K)") (class "Default")
      (node (ref "Cd24VCDE") (pin "2") (pinfunction "2_2") (pintype "passive"))
      (node (ref "Dreverse") (pin "2") (pinfunction "K_2") (pintype "passive"))
      (node (ref "TR_5V") (pin "1") (pinfunction "+Vin_1") (pintype "passive"))
    )
    (net (code "130") (name "Net-(LCD*-PadA)") (class "Default")
      (node (ref "LCD*") (pin "A") (pinfunction "A_A") (pintype "passive"))
      (node (ref "Rretro") (pin "1") (pinfunction "1_1") (pintype "passive"))
    )
    (net (code "131") (name "Net-(LCD*-V0)") (class "Default")
      (node (ref "CV0") (pin "1") (pinfunction "1_1") (pintype "passive"))
      (node (ref "LCD*") (pin "3") (pinfunction "V0_3") (pintype "passive"))
    )
    (net (code "132") (name "Net-(LCD*-V1)") (class "Default")
      (node (ref "CV1") (pin "1") (pinfunction "1_1") (pintype "passive"))
      (node (ref "LCD*") (pin "4") (pinfunction "V1_4") (pintype "passive"))
    )
    (net (code "133") (name "Net-(LCD*-V2)") (class "Default")
      (node (ref "CV2") (pin "1") (pinfunction "1_1") (pintype "passive"))
      (node (ref "LCD*") (pin "5") (pinfunction "V2_5") (pintype "passive"))
    )
    (net (code "134") (name "Net-(LCD*-V3)") (class "Default")
      (node (ref "CV3") (pin "1") (pinfunction "1_1") (pintype "passive"))
      (node (ref "LCD*") (pin "6") (pinfunction "V3_6") (pintype "passive"))
    )
    (net (code "135") (name "Net-(LCD*-V4)") (class "Default")
      (node (ref "CV4") (pin "1") (pinfunction "1_1") (pintype "passive"))
      (node (ref "LCD*") (pin "7") (pinfunction "V4_7") (pintype "passive"))
    )
    (net (code "136") (name "Net-(LCD*-VOUT)") (class "Default")
      (node (ref "CVOUT") (pin "1") (pinfunction "1_1") (pintype "passive"))
      (node (ref "LCD*") (pin "2") (pinfunction "VOUT_2") (pintype "passive"))
    )
    (net (code "137") (name "Net-(LED_color-C1)") (class "Default")
      (node (ref "LED_color") (pin "4") (pinfunction "C1_4") (pintype "passive"))
      (node (ref "RGreen") (pin "2") (pinfunction "2_2") (pintype "passive"))
    )
    (net (code "138") (name "Net-(LED_color-C2)") (class "Default")
      (node (ref "LED_color") (pin "3") (pinfunction "C2_3") (pintype "passive"))
      (node (ref "Rred") (pin "2") (pinfunction "2_2") (pintype "passive"))
    )
    (net (code "139") (name "Net-(LED_color-C3)") (class "Default")
      (node (ref "LED_color") (pin "2") (pinfunction "C3_2") (pintype "passive"))
      (node (ref "RBlue") (pin "2") (pinfunction "2_2") (pintype "passive"))
    )
    (net (code "140") (name "Net-(Led0-A)") (class "Default")
      (node (ref "Led0") (pin "1") (pinfunction "A_1") (pintype "passive"))
      (node (ref "Rled0") (pin "1") (pinfunction "1_1") (pintype "passive"))
    )
    (net (code "141") (name "Net-(Led1-A)") (class "Default")
      (node (ref "Led1") (pin "1") (pinfunction "A_1") (pintype "passive"))
      (node (ref "Rled1") (pin "1") (pinfunction "1_1") (pintype "passive"))
    )
    (net (code "142") (name "Net-(Led2-A)") (class "Default")
      (node (ref "Led2") (pin "1") (pinfunction "A_1") (pintype "passive"))
      (node (ref "Rled2") (pin "1") (pinfunction "1_1") (pintype "passive"))
    )
    (net (code "143") (name "Net-(Led3-A)") (class "Default")
      (node (ref "Led3") (pin "1") (pinfunction "A_1") (pintype "passive"))
      (node (ref "Rled3") (pin "1") (pinfunction "1_1") (pintype "passive"))
    )
    (net (code "144") (name "Net-(Led4-A)") (class "Default")
      (node (ref "Led4") (pin "1") (pinfunction "A_1") (pintype "passive"))
      (node (ref "Rled4") (pin "1") (pinfunction "1_1") (pintype "passive"))
    )
    (net (code "145") (name "Net-(Led5-A)") (class "Default")
      (node (ref "Led5") (pin "1") (pinfunction "A_1") (pintype "passive"))
      (node (ref "Rled5") (pin "1") (pinfunction "1_1") (pintype "passive"))
    )
    (net (code "146") (name "Net-(RledBir-Pad1)") (class "Default")
      (node (ref "RledBir") (pin "1") (pinfunction "1_1") (pintype "passive"))
      (node (ref "birouteLed") (pin "1") (pinfunction "1_1") (pintype "passive"))
    )
    (net (code "147") (name "Net-(Rmes12+-Pad1)") (class "Default")
      (node (ref "Rmes12+") (pin "1") (pinfunction "1_1") (pintype "passive"))
      (node (ref "Rmes12-") (pin "2") (pinfunction "2_2") (pintype "passive"))
      (node (ref "Rsme12") (pin "1") (pinfunction "1_1") (pintype "passive"))
    )
    (net (code "148") (name "Net-(Rmes24+-Pad1)") (class "Default")
      (node (ref "Rmes24+") (pin "1") (pinfunction "1_1") (pintype "passive"))
      (node (ref "Rmes24-") (pin "2") (pinfunction "2_2") (pintype "passive"))
      (node (ref "Rsme24") (pin "1") (pinfunction "1_1") (pintype "passive"))
    )
    (net (code "149") (name "Net-(Rmes24p+-Pad1)") (class "Default")
      (node (ref "Rmes24p+") (pin "1") (pinfunction "1_1") (pintype "passive"))
      (node (ref "Rmes24p-") (pin "2") (pinfunction "2_2") (pintype "passive"))
      (node (ref "Rsme24p") (pin "1") (pinfunction "1_1") (pintype "passive"))
    )
    (net (code "150") (name "Net-(RpuBir-Pad1)") (class "Default")
      (node (ref "RpuBir") (pin "1") (pinfunction "1_1") (pintype "passive"))
      (node (ref "RsBir") (pin "1") (pinfunction "1_1") (pintype "passive"))
      (node (ref "biroute") (pin "1") (pinfunction "1_1") (pintype "passive"))
    )
    (net (code "151") (name "Net-(RpuSW0-Pad1)") (class "Default")
      (node (ref "RpuSW0") (pin "1") (pinfunction "1_1") (pintype "passive"))
      (node (ref "RsSW0") (pin "1") (pinfunction "1_1") (pintype "passive"))
      (node (ref "SW0") (pin "NC1") (pinfunction "NC1_NC1") (pintype "passive"))
    )
    (net (code "152") (name "Net-(RpuSW1-Pad1)") (class "Default")
      (node (ref "RpuSW1") (pin "1") (pinfunction "1_1") (pintype "passive"))
      (node (ref "RsSW1") (pin "1") (pinfunction "1_1") (pintype "passive"))
      (node (ref "SW1") (pin "NC1") (pinfunction "NC1_NC1") (pintype "passive"))
    )
    (net (code "153") (name "Net-(RpuSW2-Pad1)") (class "Default")
      (node (ref "RpuSW2") (pin "1") (pinfunction "1_1") (pintype "passive"))
      (node (ref "RsSW2") (pin "1") (pinfunction "1_1") (pintype "passive"))
      (node (ref "SW2") (pin "NC1") (pinfunction "NC1_NC1") (pintype "passive"))
    )
    (net (code "154") (name "Net-(RpuSW3-Pad1)") (class "Default")
      (node (ref "RpuSW3") (pin "1") (pinfunction "1_1") (pintype "passive"))
      (node (ref "RsSW3") (pin "1") (pinfunction "1_1") (pintype "passive"))
      (node (ref "SW3") (pin "NC1") (pinfunction "NC1_NC1") (pintype "passive"))
    )
    (net (code "155") (name "Net-(RpuSW4-Pad1)") (class "Default")
      (node (ref "RpuSW4") (pin "1") (pinfunction "1_1") (pintype "passive"))
      (node (ref "RsSW4") (pin "1") (pinfunction "1_1") (pintype "passive"))
      (node (ref "SW4") (pin "NC1") (pinfunction "NC1_NC1") (pintype "passive"))
    )
    (net (code "156") (name "Net-(RpuSW5-Pad1)") (class "Default")
      (node (ref "RpuSW5") (pin "1") (pinfunction "1_1") (pintype "passive"))
      (node (ref "RsSW5") (pin "1") (pinfunction "1_1") (pintype "passive"))
      (node (ref "SW5") (pin "NC1") (pinfunction "NC1_NC1") (pintype "passive"))
    )
    (net (code "157") (name "Net-(RpuSW6-Pad1)") (class "Default")
      (node (ref "RpuSW6") (pin "1") (pinfunction "1_1") (pintype "passive"))
      (node (ref "RsSW6") (pin "1") (pinfunction "1_1") (pintype "passive"))
      (node (ref "SW6") (pin "NC1") (pinfunction "NC1_NC1") (pintype "passive"))
    )
    (net (code "158") (name "Net-(RpuSW7-Pad1)") (class "Default")
      (node (ref "RpuSW7") (pin "1") (pinfunction "1_1") (pintype "passive"))
      (node (ref "RsSW7") (pin "1") (pinfunction "1_1") (pintype "passive"))
      (node (ref "SW7") (pin "NC1") (pinfunction "NC1_NC1") (pintype "passive"))
    )
    (net (code "159") (name "Net-(RpuSW8-Pad1)") (class "Default")
      (node (ref "RpuSW8") (pin "1") (pinfunction "1_1") (pintype "passive"))
      (node (ref "RsSW8") (pin "1") (pinfunction "1_1") (pintype "passive"))
      (node (ref "SW8") (pin "NC1") (pinfunction "NC1_NC1") (pintype "passive"))
    )
    (net (code "160") (name "Net-(RpuSW9-Pad1)") (class "Default")
      (node (ref "RpuSW9") (pin "1") (pinfunction "1_1") (pintype "passive"))
      (node (ref "RsSW9") (pin "1") (pinfunction "1_1") (pintype "passive"))
      (node (ref "SW9") (pin "NC1") (pinfunction "NC1_NC1") (pintype "passive"))
    )
    (net (code "161") (name "Net-(RpuSW10-Pad1)") (class "Default")
      (node (ref "RpuSW10") (pin "1") (pinfunction "1_1") (pintype "passive"))
      (node (ref "RsSW10") (pin "1") (pinfunction "1_1") (pintype "passive"))
      (node (ref "SW10") (pin "NC1") (pinfunction "NC1_NC1") (pintype "passive"))
    )
    (net (code "162") (name "Net-(RpuSW11-Pad1)") (class "Default")
      (node (ref "RpuSW11") (pin "1") (pinfunction "1_1") (pintype "passive"))
      (node (ref "RsSW11") (pin "1") (pinfunction "1_1") (pintype "passive"))
      (node (ref "SW11") (pin "NC1") (pinfunction "NC1_NC1") (pintype "passive"))
    )
    (net (code "163") (name "Net-(RpuSW12-Pad1)") (class "Default")
      (node (ref "RpuSW12") (pin "1") (pinfunction "1_1") (pintype "passive"))
      (node (ref "RsSW12") (pin "1") (pinfunction "1_1") (pintype "passive"))
      (node (ref "SW12") (pin "NC1") (pinfunction "NC1_NC1") (pintype "passive"))
    )
    (net (code "164") (name "Net-(RpuSW13-Pad1)") (class "Default")
      (node (ref "RpuSW13") (pin "1") (pinfunction "1_1") (pintype "passive"))
      (node (ref "RsSW13") (pin "1") (pinfunction "1_1") (pintype "passive"))
      (node (ref "SW13") (pin "NC1") (pinfunction "NC1_NC1") (pintype "passive"))
    )
    (net (code "165") (name "Net-(RpuSW14-Pad1)") (class "Default")
      (node (ref "RpuSW14") (pin "1") (pinfunction "1_1") (pintype "passive"))
      (node (ref "RsSW14") (pin "1") (pinfunction "1_1") (pintype "passive"))
      (node (ref "SW14") (pin "NC1") (pinfunction "NC1_NC1") (pintype "passive"))
    )
    (net (code "166") (name "Net-(RpuSW15-Pad1)") (class "Default")
      (node (ref "RpuSW15") (pin "1") (pinfunction "1_1") (pintype "passive"))
      (node (ref "RsSW15") (pin "1") (pinfunction "1_1") (pintype "passive"))
      (node (ref "SW15") (pin "NC1") (pinfunction "NC1_NC1") (pintype "passive"))
    )
    (net (code "167") (name "Net-(RpuSW16-Pad1)") (class "Default")
      (node (ref "RpuSW16") (pin "1") (pinfunction "1_1") (pintype "passive"))
      (node (ref "RsSW16") (pin "1") (pinfunction "1_1") (pintype "passive"))
      (node (ref "SW16") (pin "NC1") (pinfunction "NC1_NC1") (pintype "passive"))
    )
    (net (code "168") (name "Net-(RpuSW17-Pad1)") (class "Default")
      (node (ref "RpuSW17") (pin "1") (pinfunction "1_1") (pintype "passive"))
      (node (ref "RsSW17") (pin "1") (pinfunction "1_1") (pintype "passive"))
      (node (ref "SW17") (pin "NC1") (pinfunction "NC1_NC1") (pintype "passive"))
    )
    (net (code "169") (name "Net-(RpuSW18-Pad1)") (class "Default")
      (node (ref "RpuSW18") (pin "1") (pinfunction "1_1") (pintype "passive"))
      (node (ref "RsSW18") (pin "1") (pinfunction "1_1") (pintype "passive"))
      (node (ref "SW18") (pin "NC1") (pinfunction "NC1_NC1") (pintype "passive"))
    )
    (net (code "170") (name "Net-(RpuSWcolor-Pad1)") (class "Default")
      (node (ref "RpuSWcolor") (pin "1") (pinfunction "1_1") (pintype "passive"))
      (node (ref "RsSWcolor") (pin "1") (pinfunction "1_1") (pintype "passive"))
      (node (ref "SWcolor") (pin "NC1") (pinfunction "NC1_NC1") (pintype "passive"))
    )
    (net (code "171") (name "Net-(RpuSWlcd-Pad1)") (class "Default")
      (node (ref "RpuSWlcd") (pin "1") (pinfunction "1_1") (pintype "passive"))
      (node (ref "RsSWlcd") (pin "1") (pinfunction "1_1") (pintype "passive"))
      (node (ref "SWlcd") (pin "NC1") (pinfunction "NC1_NC1") (pintype "passive"))
    )
    (net (code "172") (name "Net-(STM32A-PH0-OSC_IN(PH0))") (class "Default")
      (node (ref "C46") (pin "2") (pinfunction "2_2") (pintype "passive"))
      (node (ref "STM32") (pin "12") (pinfunction "PH0-OSC_IN(PH0)_12") (pintype "bidirectional"))
      (node (ref "Y1") (pin "2") (pinfunction "OSC2_2") (pintype "passive"))
    )
    (net (code "173") (name "Net-(STM32A-PH1-OSC_OUT(PH1))") (class "Default")
      (node (ref "C47") (pin "2") (pinfunction "2_2") (pintype "passive"))
      (node (ref "STM32") (pin "13") (pinfunction "PH1-OSC_OUT(PH1)_13") (pintype "bidirectional"))
      (node (ref "Y1") (pin "1") (pinfunction "OSC1_1") (pintype "passive"))
    )
    (net (code "174") (name "Net-(STM32A-VCAP_1)") (class "Default")
      (node (ref "C49") (pin "2") (pinfunction "2_2") (pintype "passive"))
      (node (ref "STM32") (pin "49") (pinfunction "VCAP_1_49") (pintype "power_in"))
    )
    (net (code "175") (name "Net-(STM32A-VCAP_2)") (class "Default")
      (node (ref "C50") (pin "2") (pinfunction "2_2") (pintype "passive"))
      (node (ref "STM32") (pin "73") (pinfunction "VCAP_2_73") (pintype "power_in"))
    )
    (net (code "176") (name "Net-(STR_RpuU1tx-Pad1)") (class "Default")
      (node (ref "STR_RpuU1tx") (pin "1") (pinfunction "1_1") (pintype "passive"))
      (node (ref "STR_RsU1tx") (pin "1") (pinfunction "1_1") (pintype "passive"))
      (node (ref "STR_UART1") (pin "3") (pinfunction "3_3") (pintype "passive"))
    )
    (net (code "177") (name "Net-(STR_Rsu1rx-Pad2)") (class "Default")
      (node (ref "STR_Rsu1rx") (pin "2") (pinfunction "2_2") (pintype "passive"))
      (node (ref "STR_UART1") (pin "4") (pinfunction "4_4") (pintype "passive"))
    )
    (net (code "178") (name "unconnected-(BP0-Pad1)") (class "Default")
      (node (ref "BP0") (pin "1") (pinfunction "1_1") (pintype "passive"))
    )
    (net (code "179") (name "unconnected-(BP1-Pad1)") (class "Default")
      (node (ref "BP1") (pin "1") (pinfunction "1_1") (pintype "passive"))
    )
    (net (code "180") (name "unconnected-(BP2-Pad1)") (class "Default")
      (node (ref "BP2") (pin "1") (pinfunction "1_1") (pintype "passive"))
    )
    (net (code "181") (name "unconnected-(BP3-Pad1)") (class "Default")
      (node (ref "BP3") (pin "1") (pinfunction "1_1") (pintype "passive"))
    )
    (net (code "182") (name "unconnected-(BP4-Pad1)") (class "Default")
      (node (ref "BP4") (pin "1") (pinfunction "1_1") (pintype "passive"))
    )
    (net (code "183") (name "unconnected-(BP5-Pad1)") (class "Default")
      (node (ref "BP5") (pin "1") (pinfunction "1_1") (pintype "passive"))
    )
    (net (code "184") (name "unconnected-(BP_LCD+-3-Pad2)") (class "Default")
      (node (ref "BP_LCD+") (pin "2") (pinfunction "3_2") (pintype "passive+no_connect"))
    )
    (net (code "185") (name "unconnected-(BP_LCD--3-Pad2)") (class "Default")
      (node (ref "BP_LCD-") (pin "2") (pinfunction "3_2") (pintype "passive+no_connect"))
    )
    (net (code "186") (name "unconnected-(BP_LCD_OK-3-Pad2)") (class "Default")
      (node (ref "BP_LCD_OK") (pin "2") (pinfunction "3_2") (pintype "passive+no_connect"))
    )
    (net (code "187") (name "unconnected-(BP_Set-3-Pad2)") (class "Default")
      (node (ref "BP_Set") (pin "2") (pinfunction "3_2") (pintype "passive+no_connect"))
    )
    (net (code "188") (name "unconnected-(BPc-Pad1)") (class "Default")
      (node (ref "BPc") (pin "1") (pinfunction "1_1") (pintype "passive"))
    )
    (net (code "189") (name "unconnected-(BPpm-Pad1)") (class "Default")
      (node (ref "BPpm") (pin "1") (pinfunction "1_1") (pintype "passive"))
    )
    (net (code "190") (name "unconnected-(BPrfu-Pad1)") (class "Default")
      (node (ref "BPrfu") (pin "1") (pinfunction "1_1") (pintype "passive"))
    )
    (net (code "191") (name "unconnected-(BPst-Pad1)") (class "Default")
      (node (ref "BPst") (pin "1") (pinfunction "1_1") (pintype "passive"))
    )
    (net (code "192") (name "unconnected-(STM32A-PA2-Pad25)") (class "Default")
      (node (ref "STM32") (pin "25") (pinfunction "PA2_25") (pintype "bidirectional"))
    )
    (net (code "193") (name "unconnected-(STM32A-PA8-Pad67)") (class "Default")
      (node (ref "STM32") (pin "67") (pinfunction "PA8_67") (pintype "bidirectional"))
    )
    (net (code "194") (name "unconnected-(STM32A-PA15(JTDI)-Pad77)") (class "Default")
      (node (ref "STM32") (pin "77") (pinfunction "PA15(JTDI)_77") (pintype "bidirectional"))
    )
    (net (code "195") (name "unconnected-(STM32A-PC10-Pad78)") (class "Default")
      (node (ref "STM32") (pin "78") (pinfunction "PC10_78") (pintype "bidirectional"))
    )
    (net (code "196") (name "unconnected-(STM32A-PC11-Pad79)") (class "Default")
      (node (ref "STM32") (pin "79") (pinfunction "PC11_79") (pintype "bidirectional"))
    )
    (net (code "197") (name "unconnected-(STM32A-PC12-Pad80)") (class "Default")
      (node (ref "STM32") (pin "80") (pinfunction "PC12_80") (pintype "bidirectional"))
    )
    (net (code "198") (name "unconnected-(STM32A-PC14-OSC32_IN(PC14)-Pad8)") (class "Default")
      (node (ref "STM32") (pin "8") (pinfunction "PC14-OSC32_IN(PC14)_8") (pintype "bidirectional"))
    )
    (net (code "199") (name "unconnected-(STM32A-PC15-OSC32_OUT(PC15)-Pad9)") (class "Default")
      (node (ref "STM32") (pin "9") (pinfunction "PC15-OSC32_OUT(PC15)_9") (pintype "bidirectional"))
    )
    (net (code "200") (name "unconnected-(STM32A-PD5-Pad86)") (class "Default")
      (node (ref "STM32") (pin "86") (pinfunction "PD5_86") (pintype "bidirectional"))
    )
    (net (code "201") (name "unconnected-(STM32A-PD8-Pad55)") (class "Default")
      (node (ref "STM32") (pin "55") (pinfunction "PD8_55") (pintype "bidirectional"))
    )
    (net (code "202") (name "unconnected-(STM32A-PD9-Pad56)") (class "Default")
      (node (ref "STM32") (pin "56") (pinfunction "PD9_56") (pintype "bidirectional"))
    )
    (net (code "203") (name "unconnected-(STM32A-PE2-Pad1)") (class "Default")
      (node (ref "STM32") (pin "1") (pinfunction "PE2_1") (pintype "bidirectional"))
    )
    (net (code "204") (name "unconnected-(STR_UART1-Pad1)") (class "Default")
      (node (ref "STR_UART1") (pin "1") (pinfunction "1_1") (pintype "passive+no_connect"))
    )
    (net (code "205") (name "unconnected-(STR_UART1-Pad2)") (class "Default")
      (node (ref "STR_UART1") (pin "2") (pinfunction "2_2") (pintype "passive+no_connect"))
    )
    (net (code "206") (name "unconnected-(STR_Ucan-VREF-Pad5)") (class "Default")
      (node (ref "STR_Ucan") (pin "5") (pinfunction "VREF_5") (pintype "output"))
    )
    (net (code "207") (name "unconnected-(SW0-PadNO1)") (class "Default")
      (node (ref "SW0") (pin "NO1") (pinfunction "NO1_NO1") (pintype "passive+no_connect"))
    )
    (net (code "208") (name "unconnected-(SW1-PadNO1)") (class "Default")
      (node (ref "SW1") (pin "NO1") (pinfunction "NO1_NO1") (pintype "passive+no_connect"))
    )
    (net (code "209") (name "unconnected-(SW2-PadNO1)") (class "Default")
      (node (ref "SW2") (pin "NO1") (pinfunction "NO1_NO1") (pintype "passive+no_connect"))
    )
    (net (code "210") (name "unconnected-(SW3-PadNO1)") (class "Default")
      (node (ref "SW3") (pin "NO1") (pinfunction "NO1_NO1") (pintype "passive+no_connect"))
    )
    (net (code "211") (name "unconnected-(SW4-PadNO1)") (class "Default")
      (node (ref "SW4") (pin "NO1") (pinfunction "NO1_NO1") (pintype "passive+no_connect"))
    )
    (net (code "212") (name "unconnected-(SW5-PadNO1)") (class "Default")
      (node (ref "SW5") (pin "NO1") (pinfunction "NO1_NO1") (pintype "passive+no_connect"))
    )
    (net (code "213") (name "unconnected-(SW6-PadNO1)") (class "Default")
      (node (ref "SW6") (pin "NO1") (pinfunction "NO1_NO1") (pintype "passive+no_connect"))
    )
    (net (code "214") (name "unconnected-(SW7-PadNO1)") (class "Default")
      (node (ref "SW7") (pin "NO1") (pinfunction "NO1_NO1") (pintype "passive+no_connect"))
    )
    (net (code "215") (name "unconnected-(SW8-PadNO1)") (class "Default")
      (node (ref "SW8") (pin "NO1") (pinfunction "NO1_NO1") (pintype "passive+no_connect"))
    )
    (net (code "216") (name "unconnected-(SW9-PadNO1)") (class "Default")
      (node (ref "SW9") (pin "NO1") (pinfunction "NO1_NO1") (pintype "passive+no_connect"))
    )
    (net (code "217") (name "unconnected-(SW10-PadNO1)") (class "Default")
      (node (ref "SW10") (pin "NO1") (pinfunction "NO1_NO1") (pintype "passive+no_connect"))
    )
    (net (code "218") (name "unconnected-(SW11-PadNO1)") (class "Default")
      (node (ref "SW11") (pin "NO1") (pinfunction "NO1_NO1") (pintype "passive+no_connect"))
    )
    (net (code "219") (name "unconnected-(SW12-PadNO1)") (class "Default")
      (node (ref "SW12") (pin "NO1") (pinfunction "NO1_NO1") (pintype "passive+no_connect"))
    )
    (net (code "220") (name "unconnected-(SW13-PadNO1)") (class "Default")
      (node (ref "SW13") (pin "NO1") (pinfunction "NO1_NO1") (pintype "passive+no_connect"))
    )
    (net (code "221") (name "unconnected-(SW14-PadNO1)") (class "Default")
      (node (ref "SW14") (pin "NO1") (pinfunction "NO1_NO1") (pintype "passive+no_connect"))
    )
    (net (code "222") (name "unconnected-(SW15-PadNO1)") (class "Default")
      (node (ref "SW15") (pin "NO1") (pinfunction "NO1_NO1") (pintype "passive+no_connect"))
    )
    (net (code "223") (name "unconnected-(SW16-PadNO1)") (class "Default")
      (node (ref "SW16") (pin "NO1") (pinfunction "NO1_NO1") (pintype "passive+no_connect"))
    )
    (net (code "224") (name "unconnected-(SW17-PadNO1)") (class "Default")
      (node (ref "SW17") (pin "NO1") (pinfunction "NO1_NO1") (pintype "passive+no_connect"))
    )
    (net (code "225") (name "unconnected-(SW18-PadNO1)") (class "Default")
      (node (ref "SW18") (pin "NO1") (pinfunction "NO1_NO1") (pintype "passive+no_connect"))
    )
    (net (code "226") (name "unconnected-(SWcolor-PadNO1)") (class "Default")
      (node (ref "SWcolor") (pin "NO1") (pinfunction "NO1_NO1") (pintype "passive+no_connect"))
    )
    (net (code "227") (name "unconnected-(SWlcd-PadNO1)") (class "Default")
      (node (ref "SWlcd") (pin "NO1") (pinfunction "NO1_NO1") (pintype "passive+no_connect"))
    )
    (net (code "228") (name "unconnected-(TR_5V-on_off-Pad6)") (class "Default")
      (node (ref "TR_5V") (pin "6") (pinfunction "on_off_6") (pintype "passive+no_connect"))
    )
    (net (code "229") (name "unconnected-(TR_5V-trim-Pad4)") (class "Default")
      (node (ref "TR_5V") (pin "4") (pinfunction "trim_4") (pintype "passive+no_connect"))
    )
    (net (code "230") (name "unconnected-(YAHOURT-Pad7)") (class "Default")
      (node (ref "YAHOURT") (pin "7") (pinfunction "7_7") (pintype "passive+no_connect"))
    )
    (net (code "231") (name "unconnected-(YAHOURT-Pad14)") (class "Default")
      (node (ref "YAHOURT") (pin "14") (pinfunction "14_14") (pintype "passive+no_connect"))
    )
  )
)
